# soap-disp-mega.net
KiCad netlist of a schematic drawn in EasyEDA
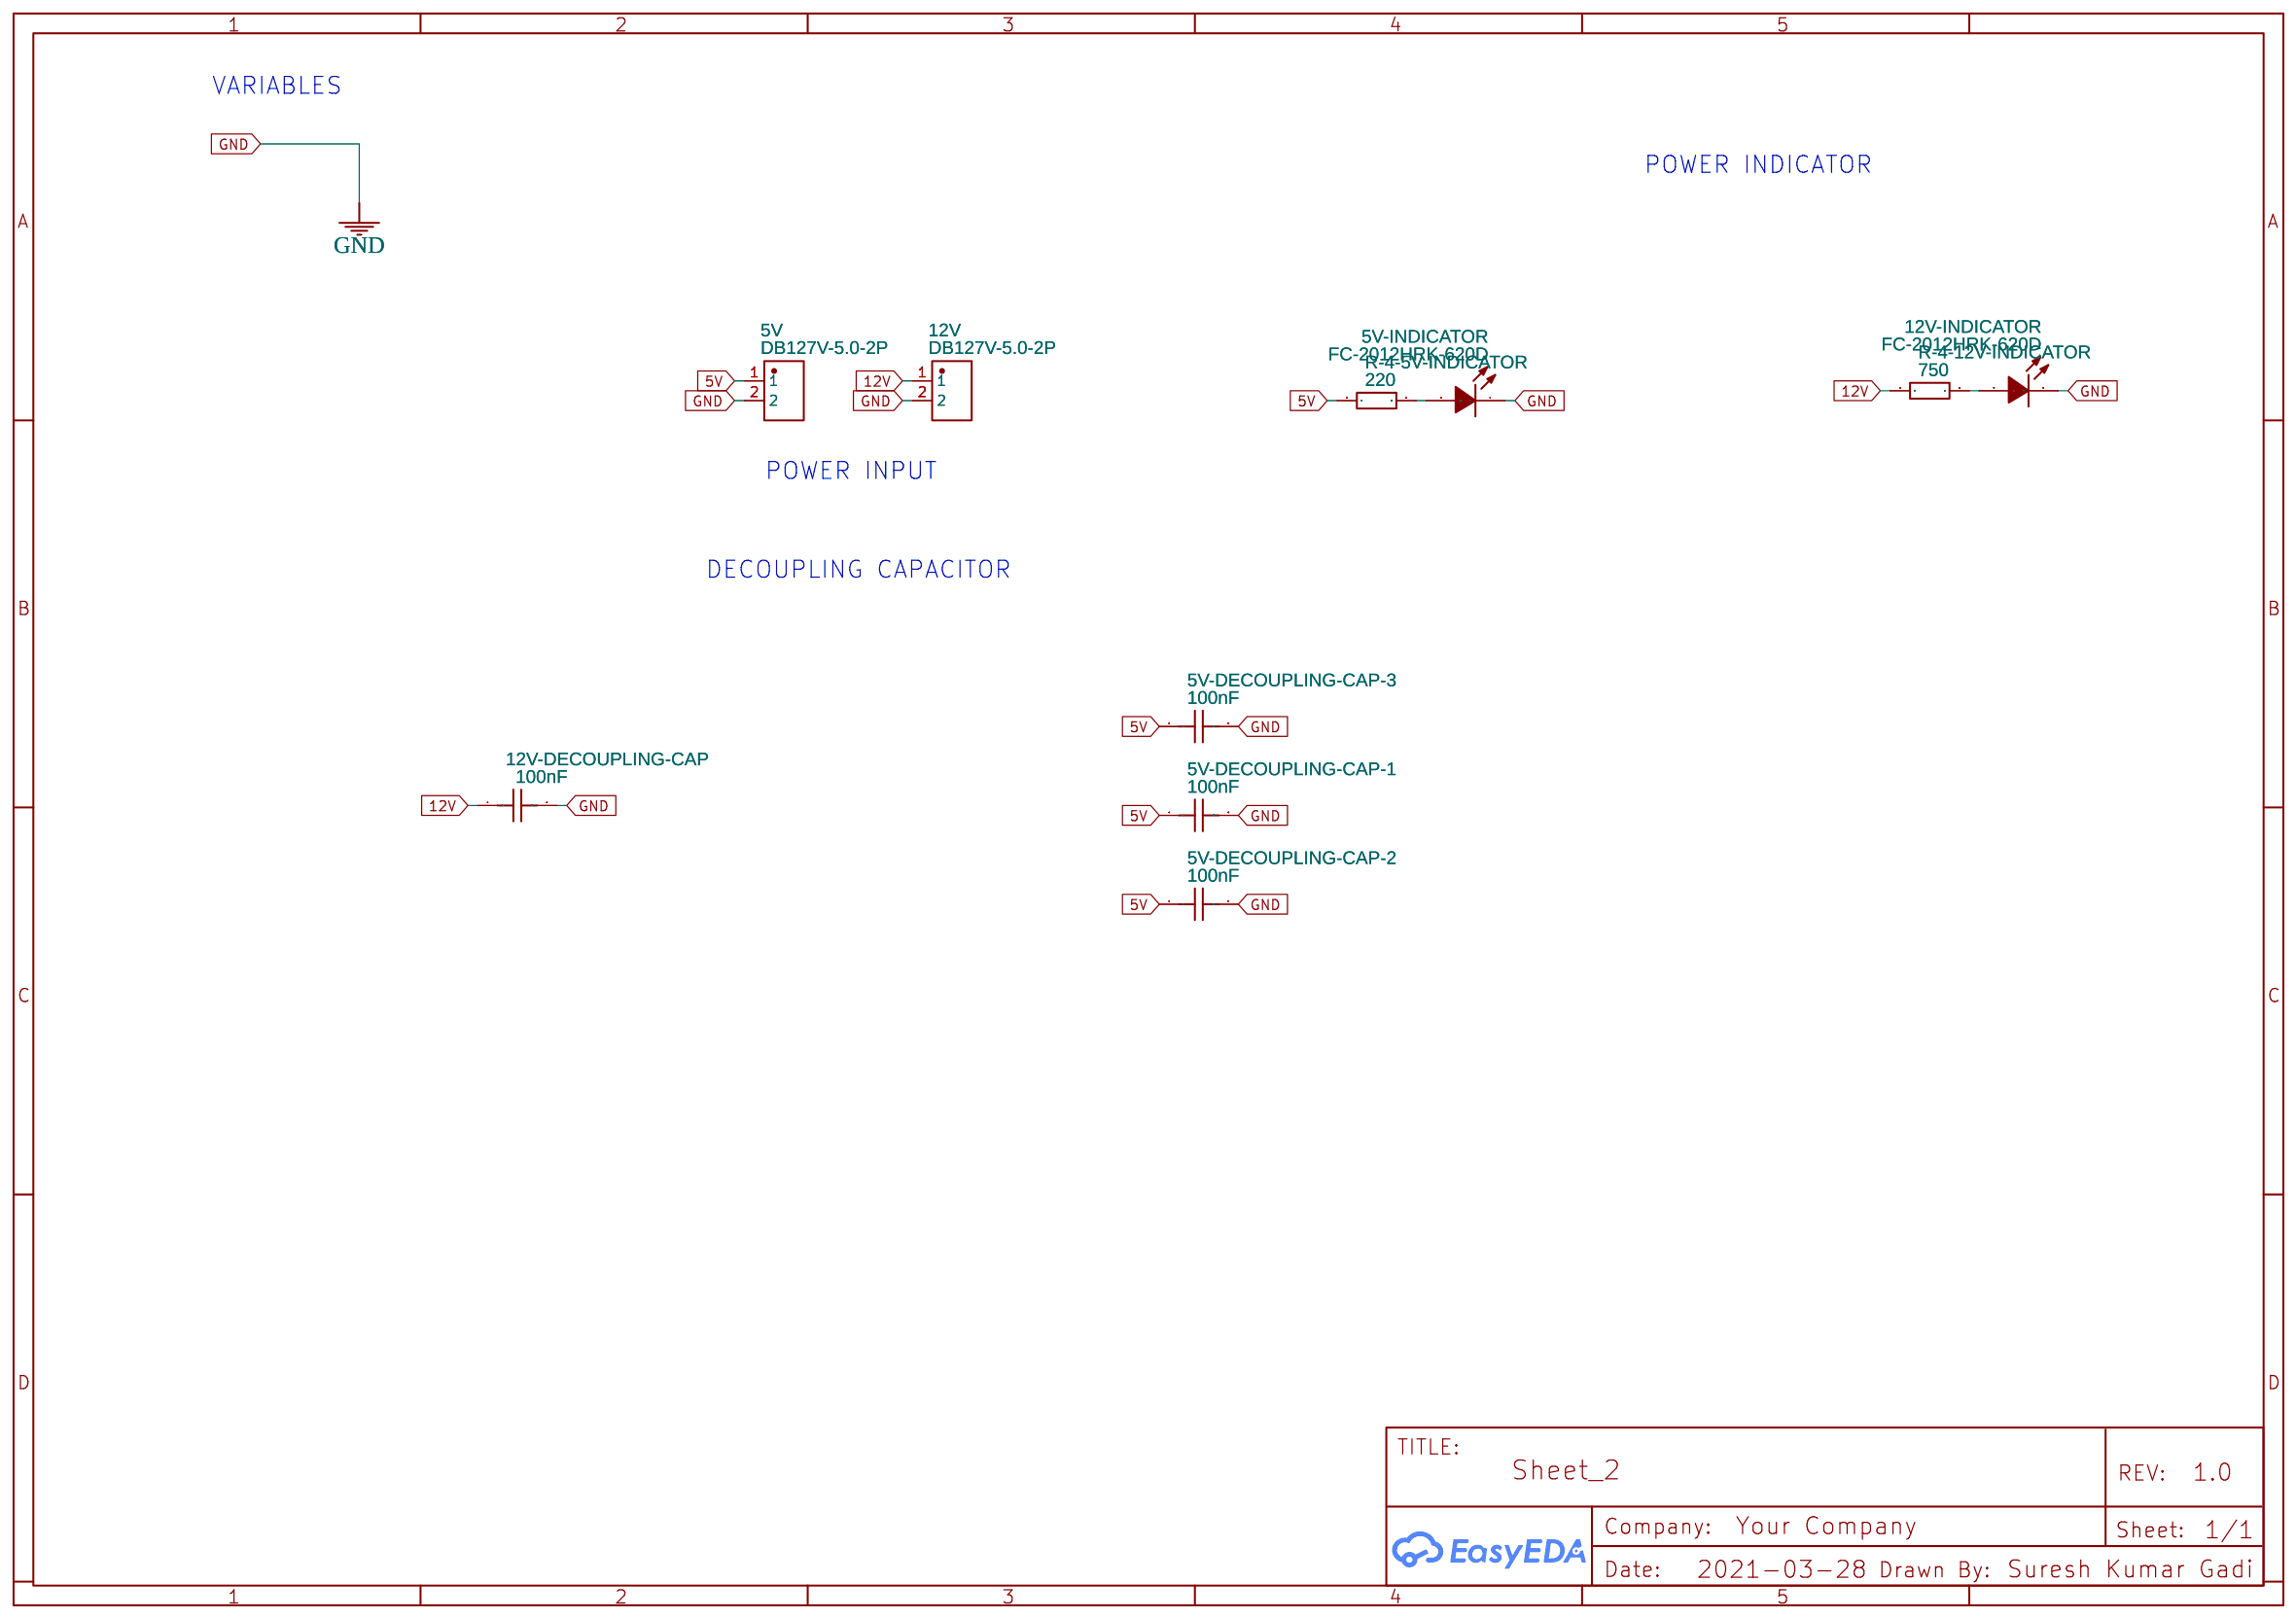
[diagram p0: Power]
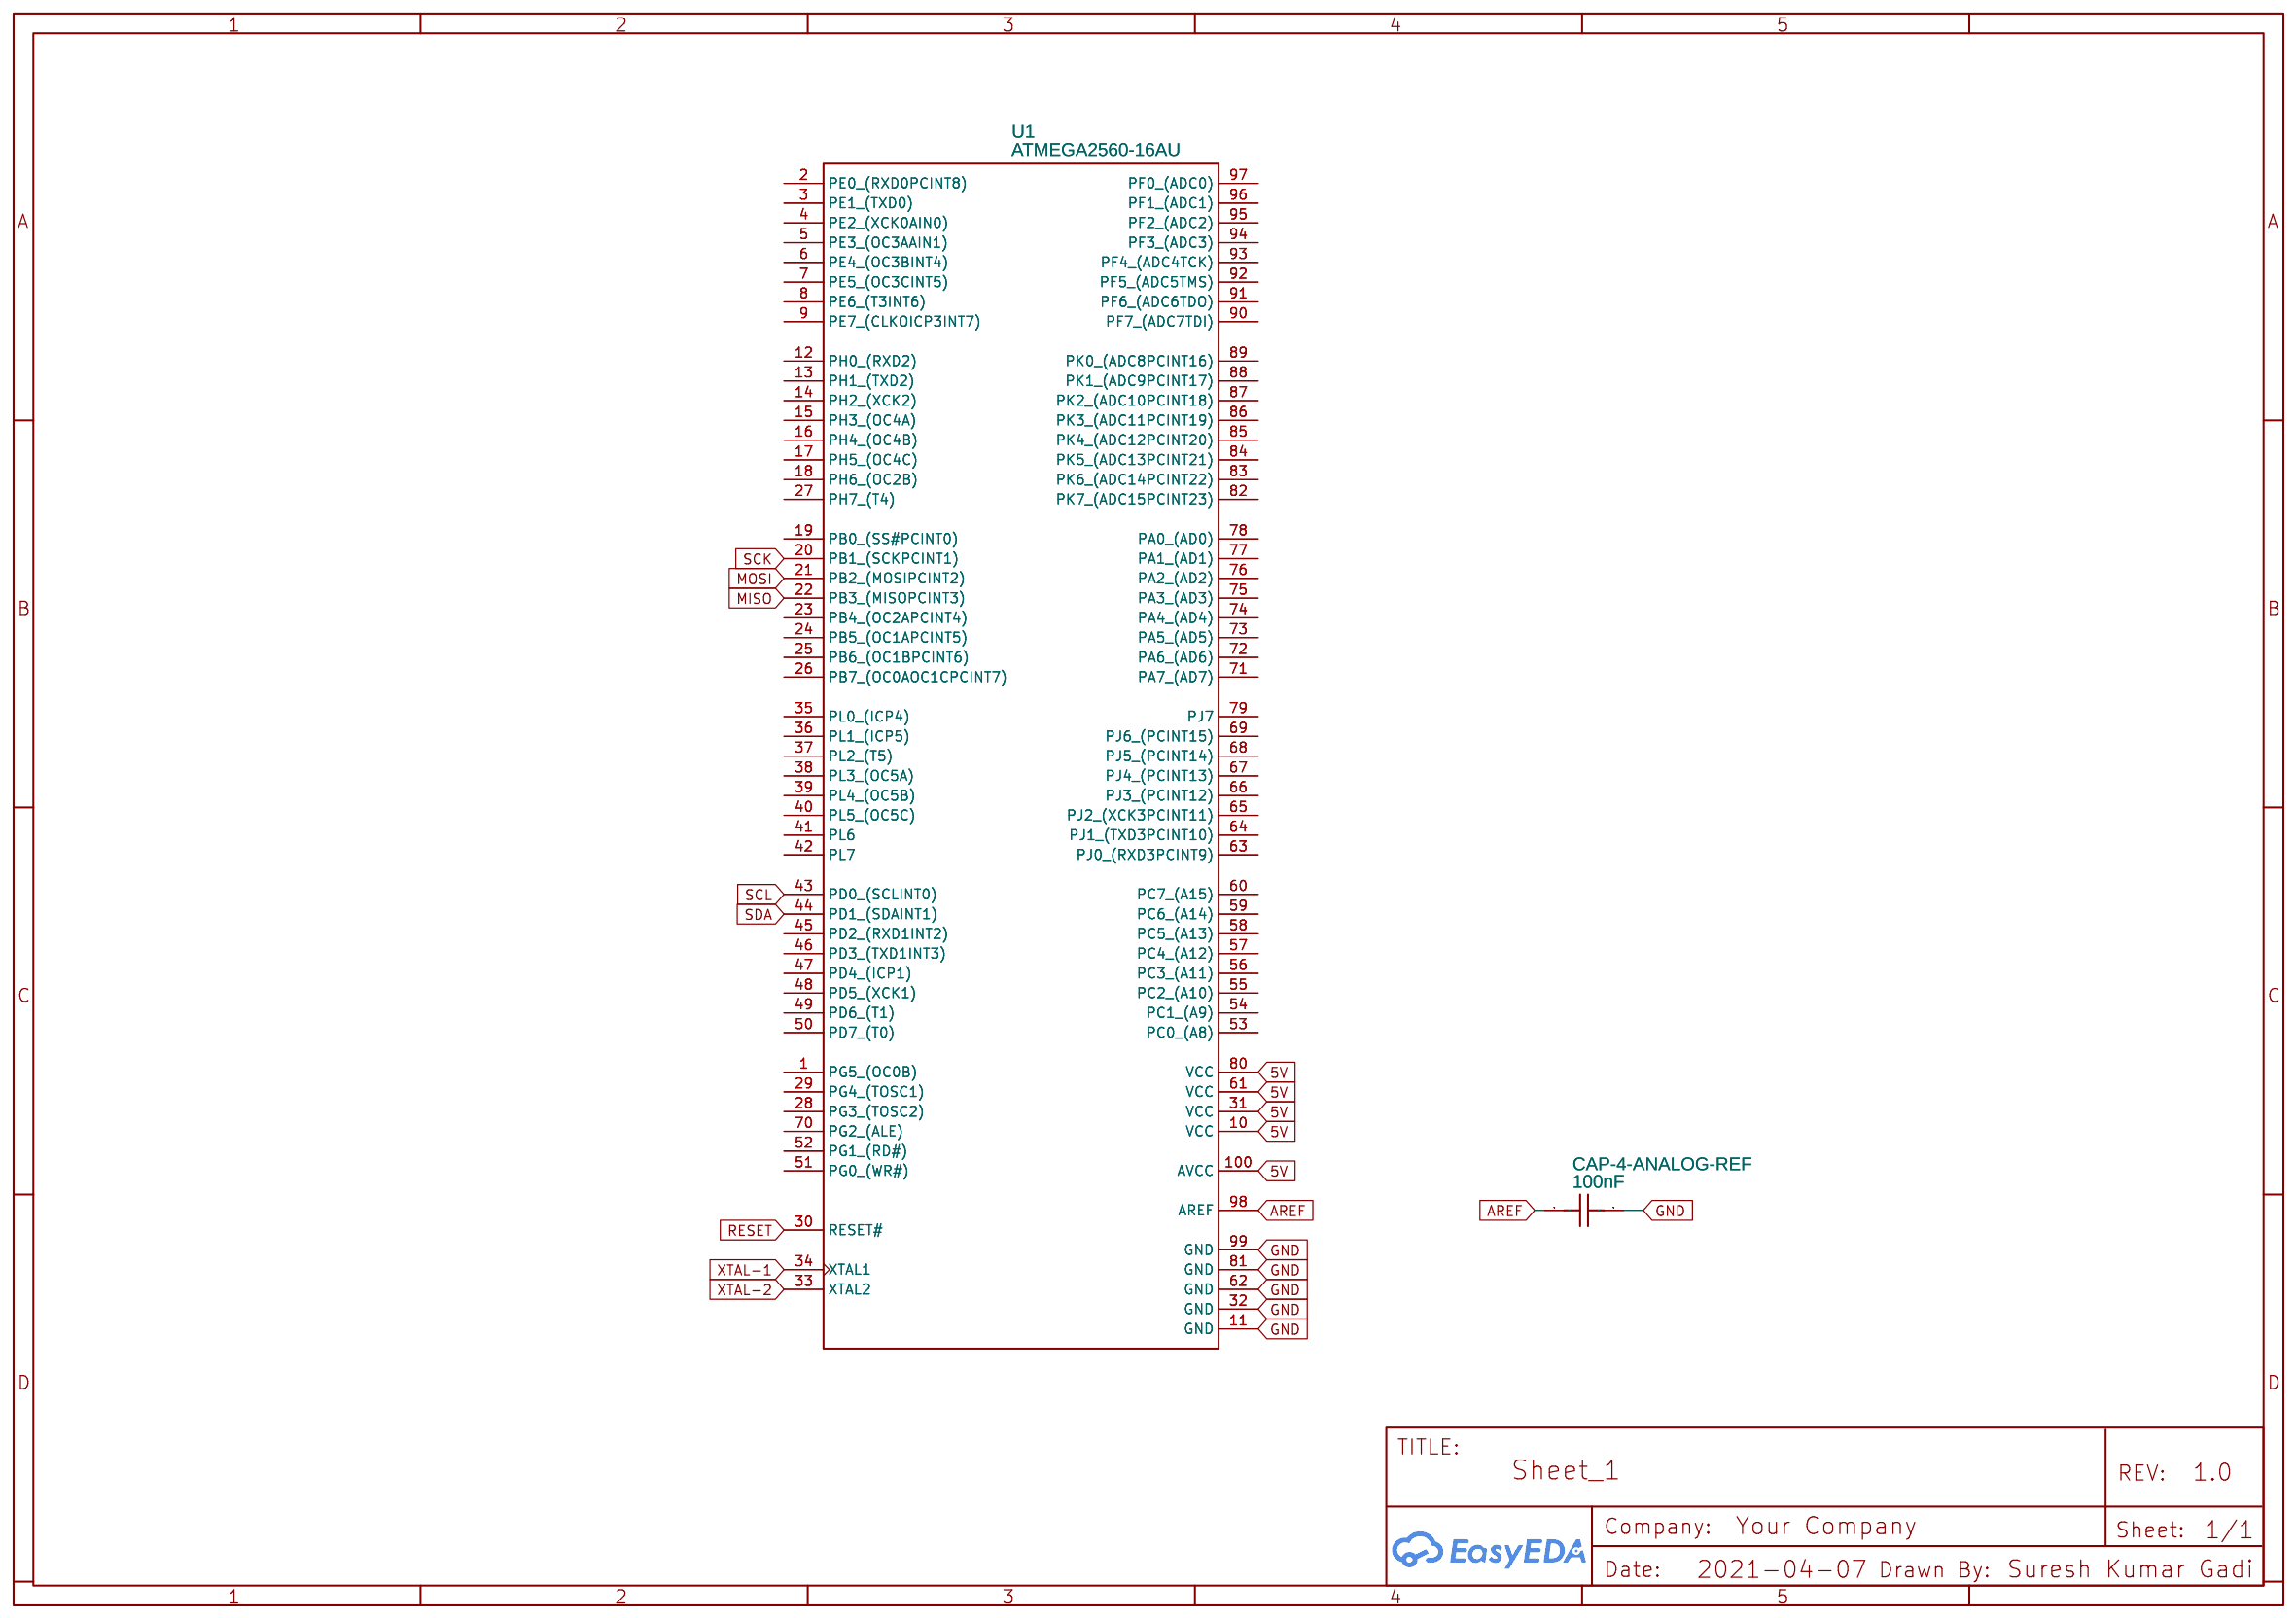
[diagram p1: Computer]
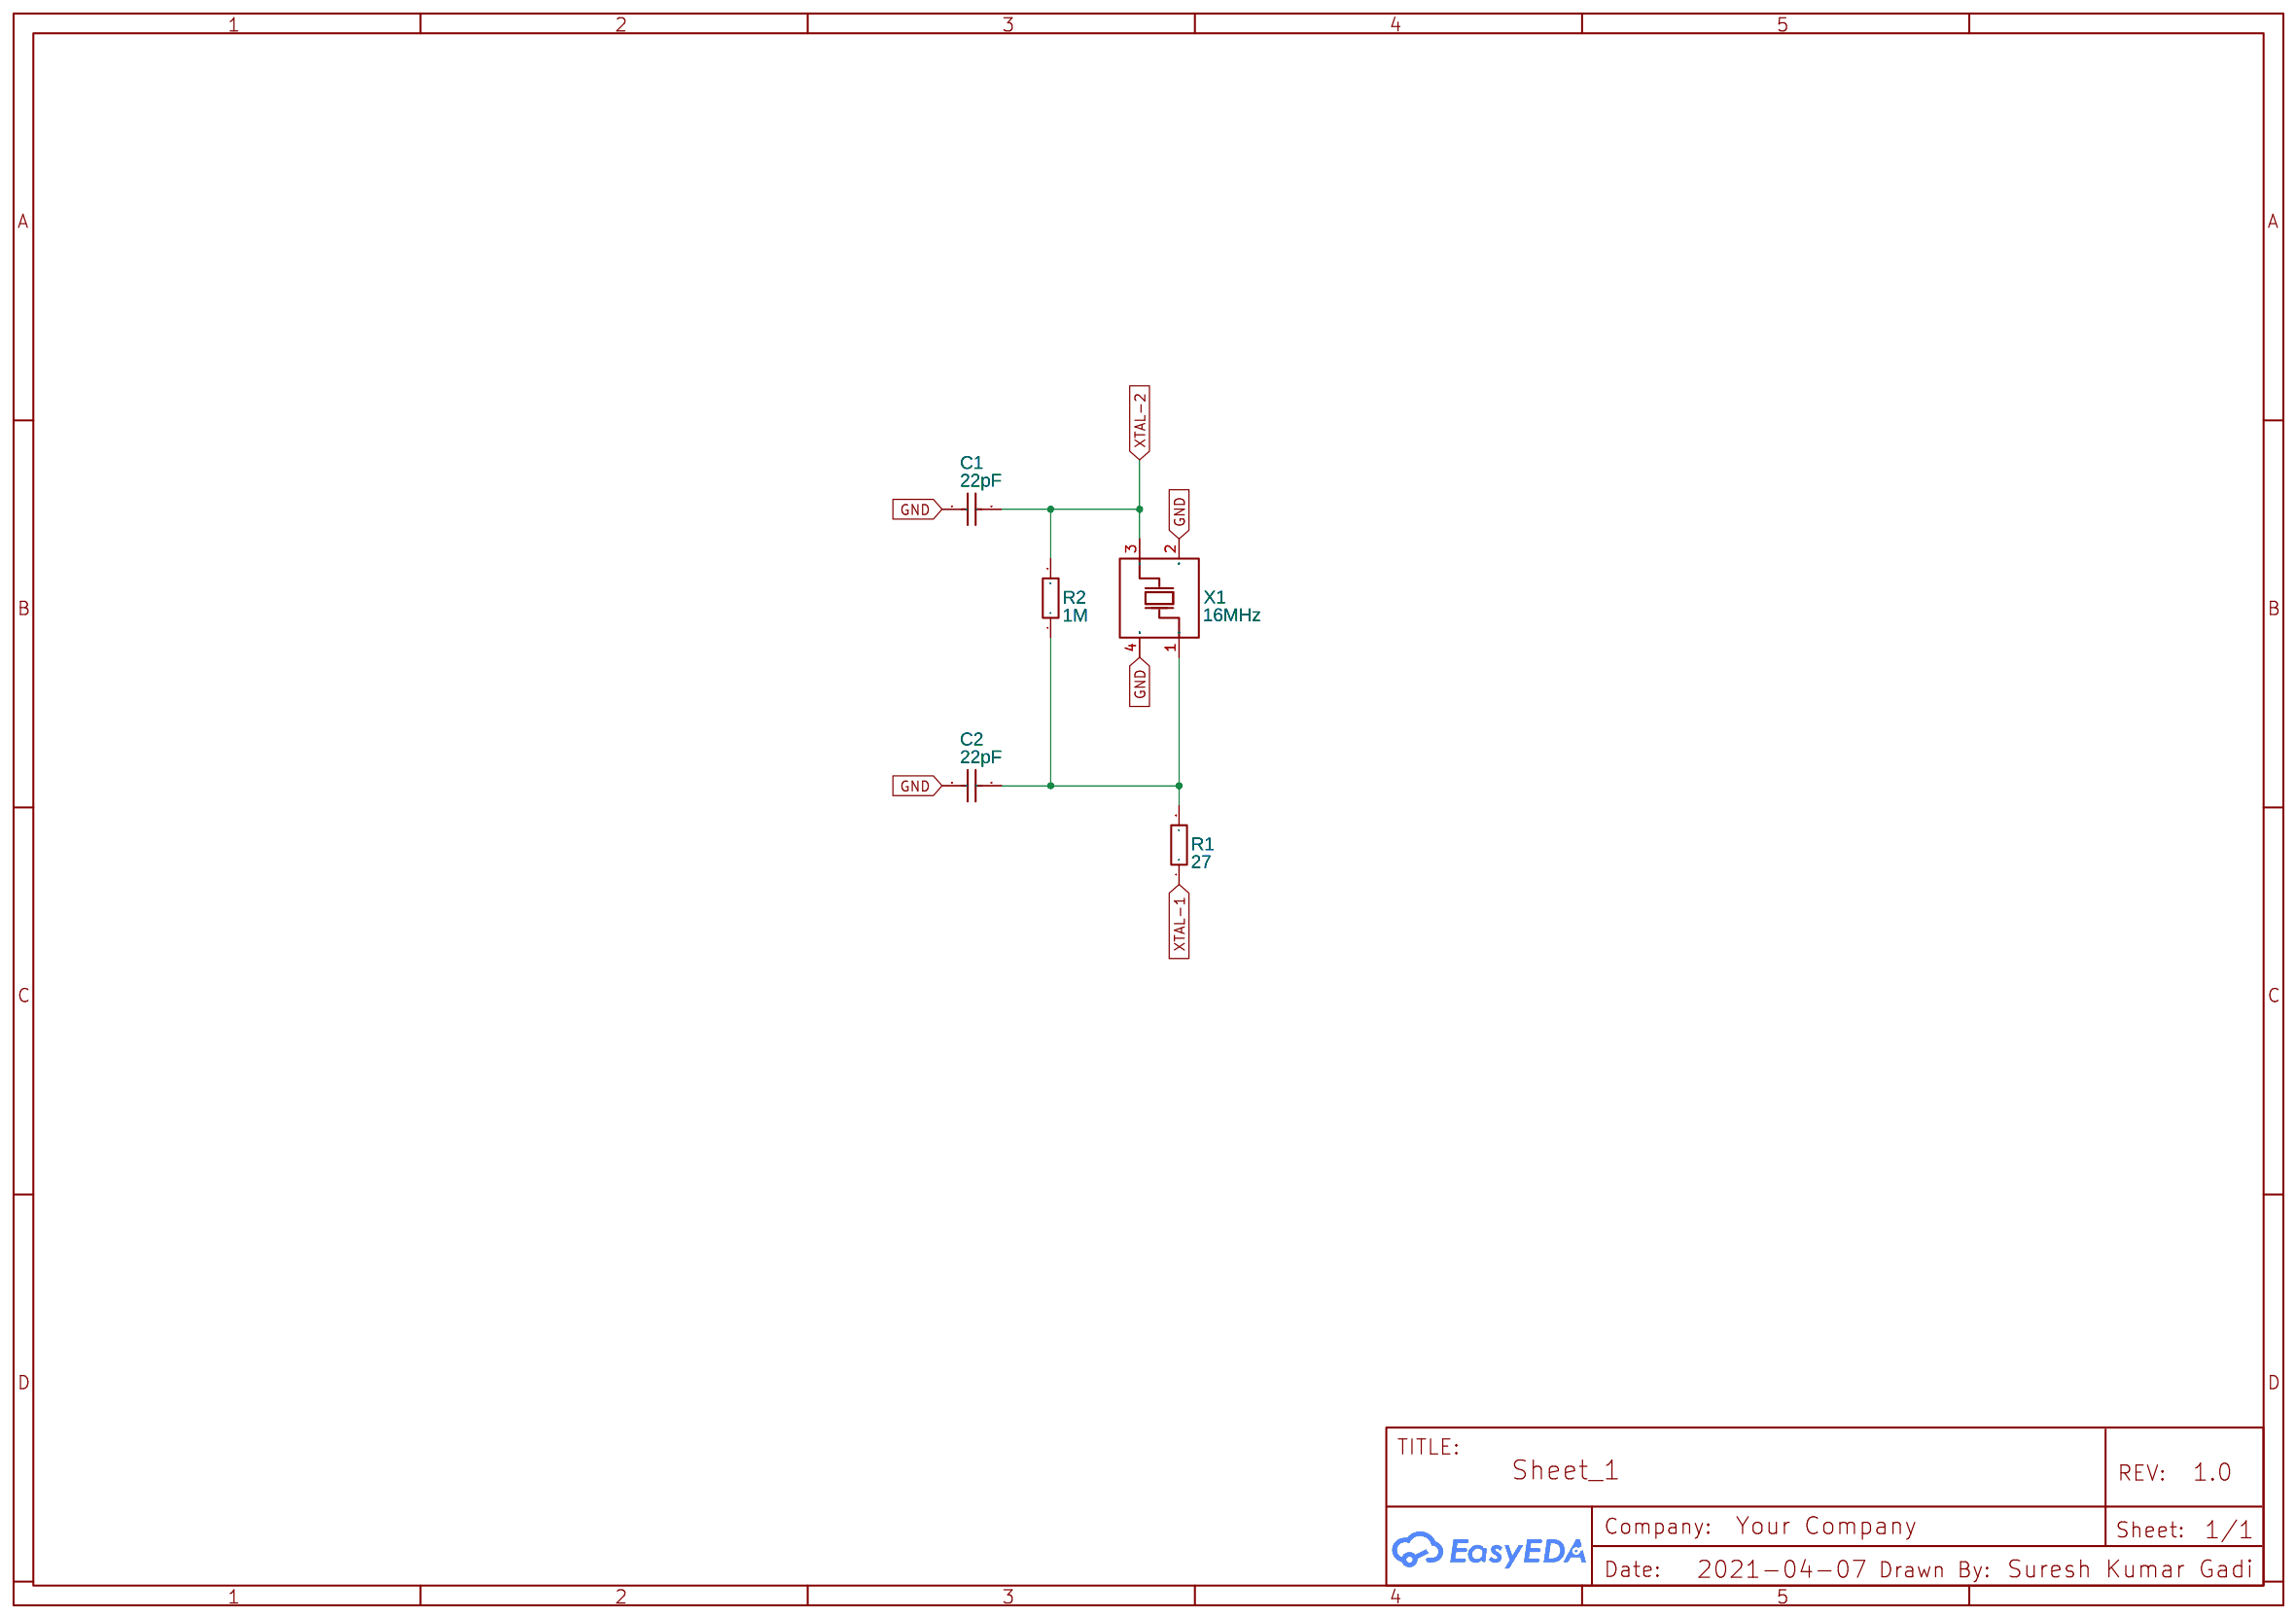
[diagram p2: Crystal]
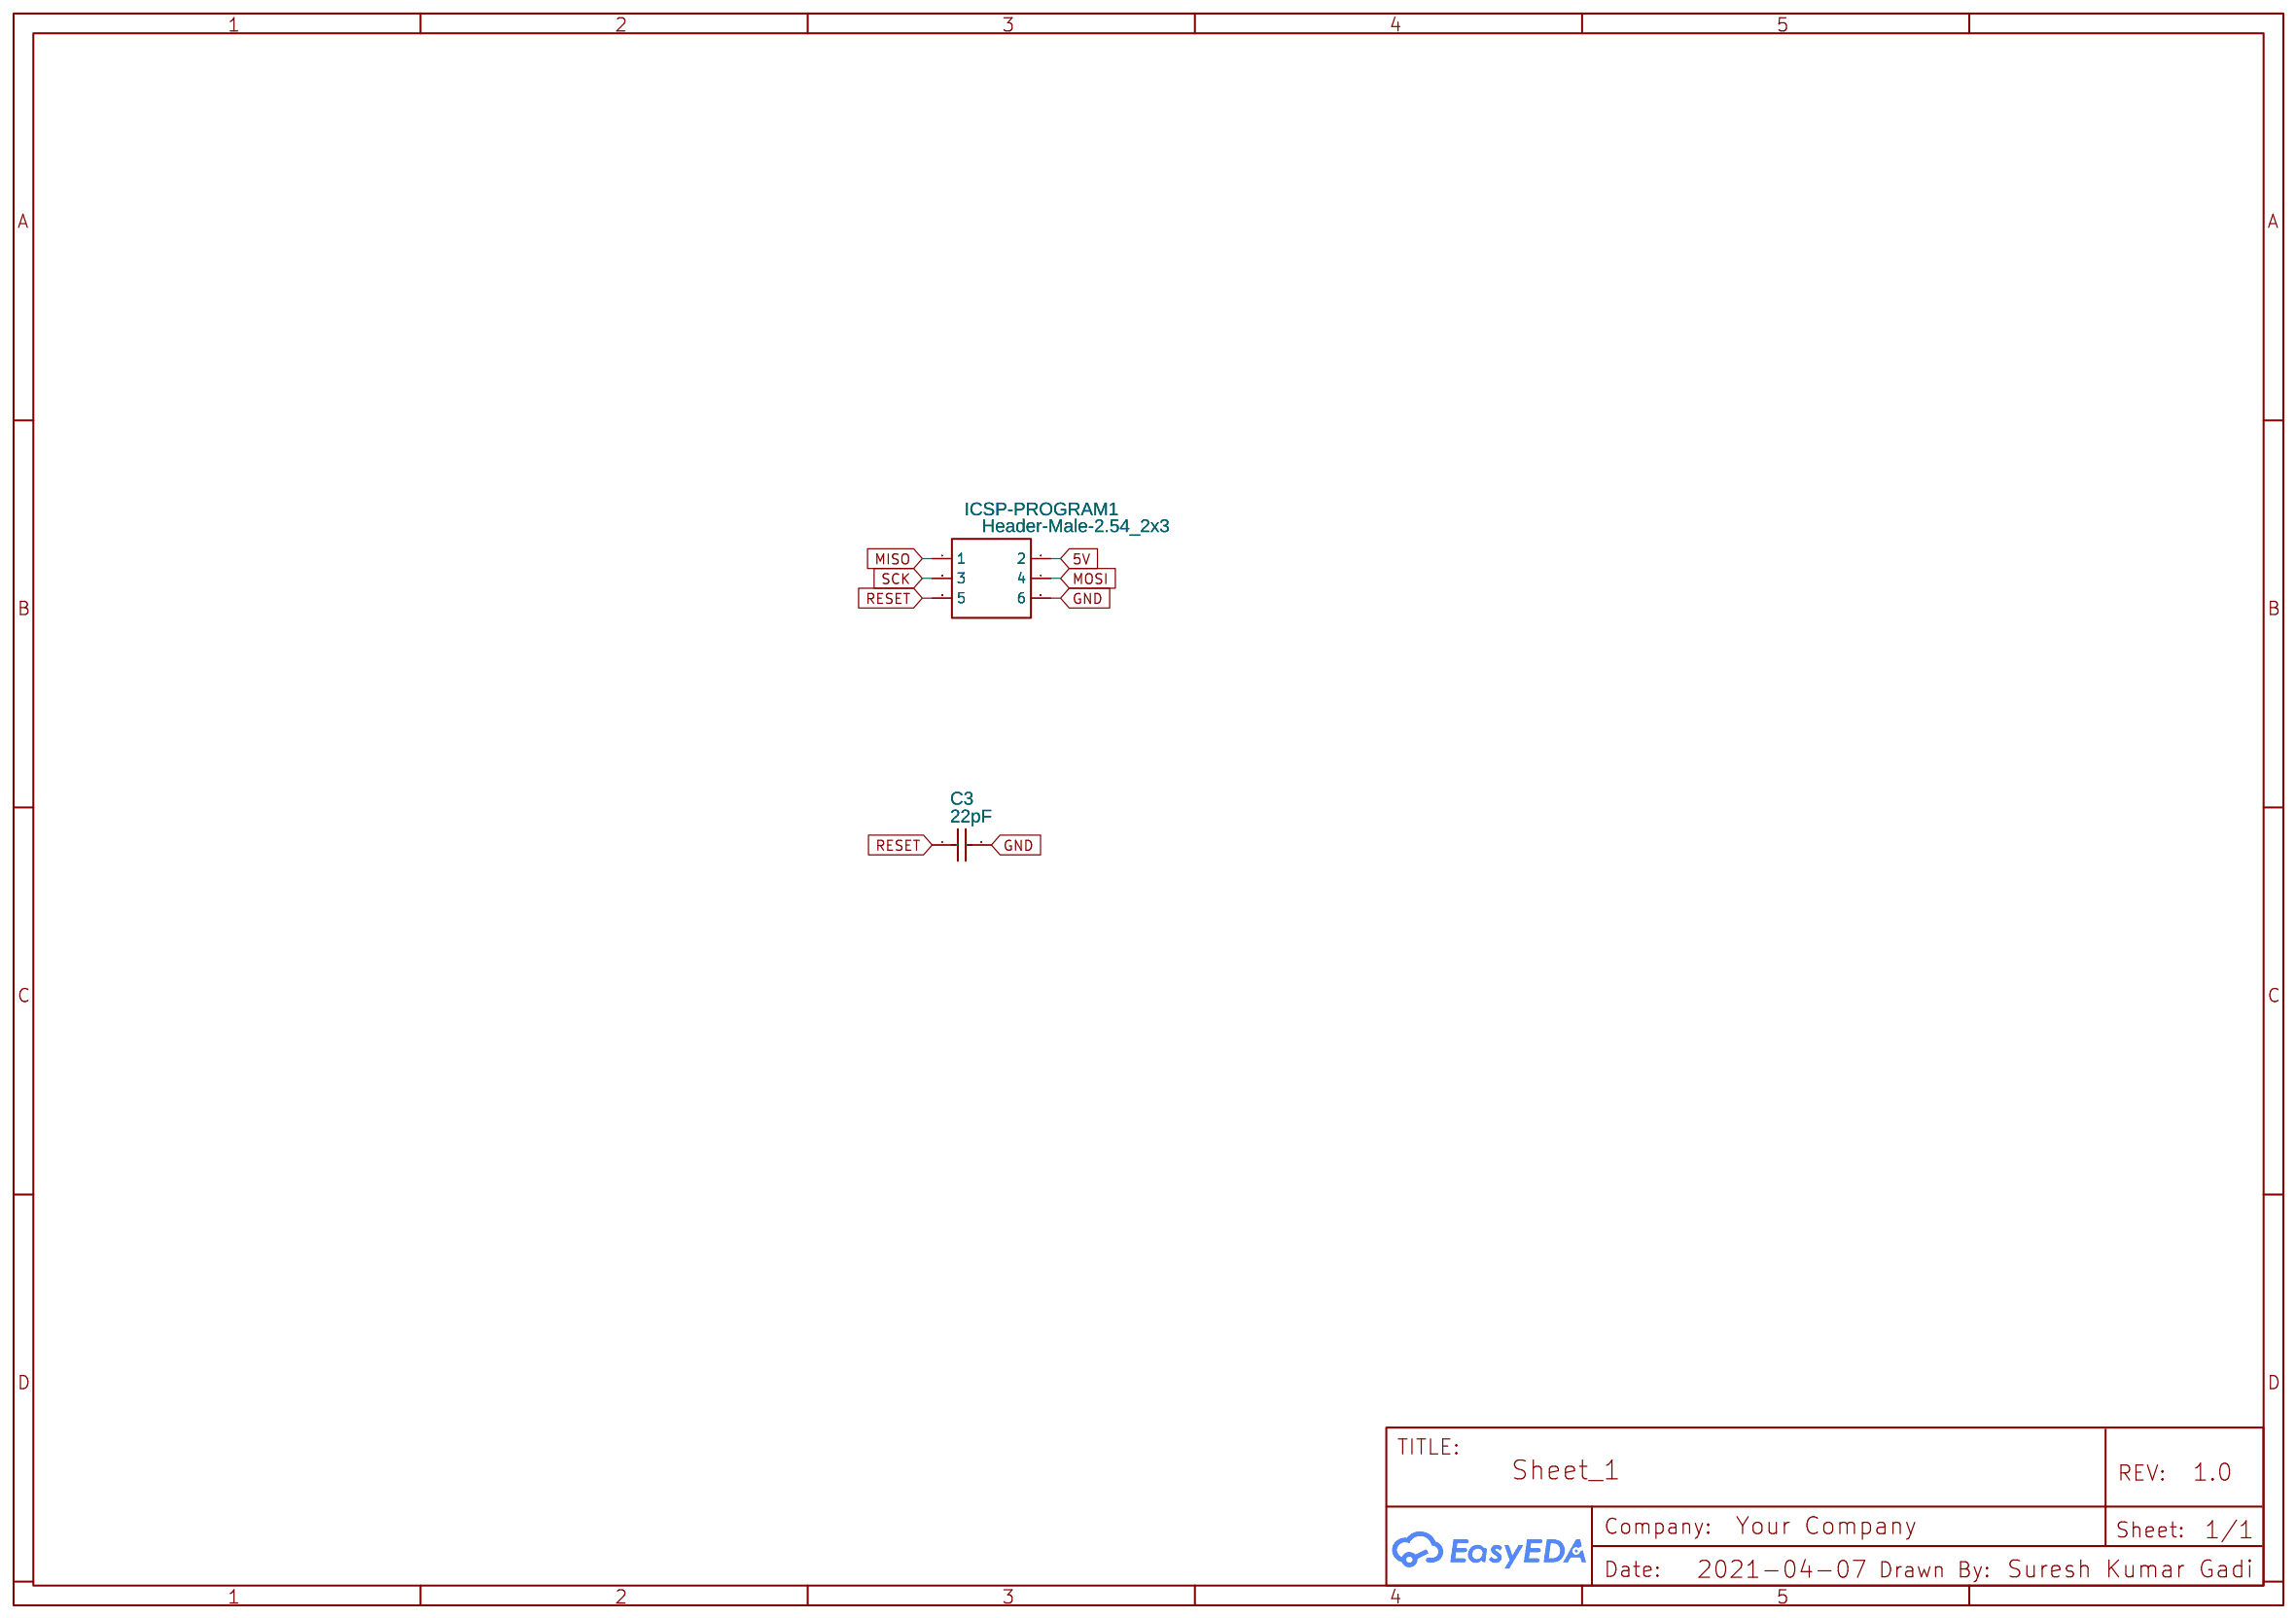
[diagram p3: ICSP]
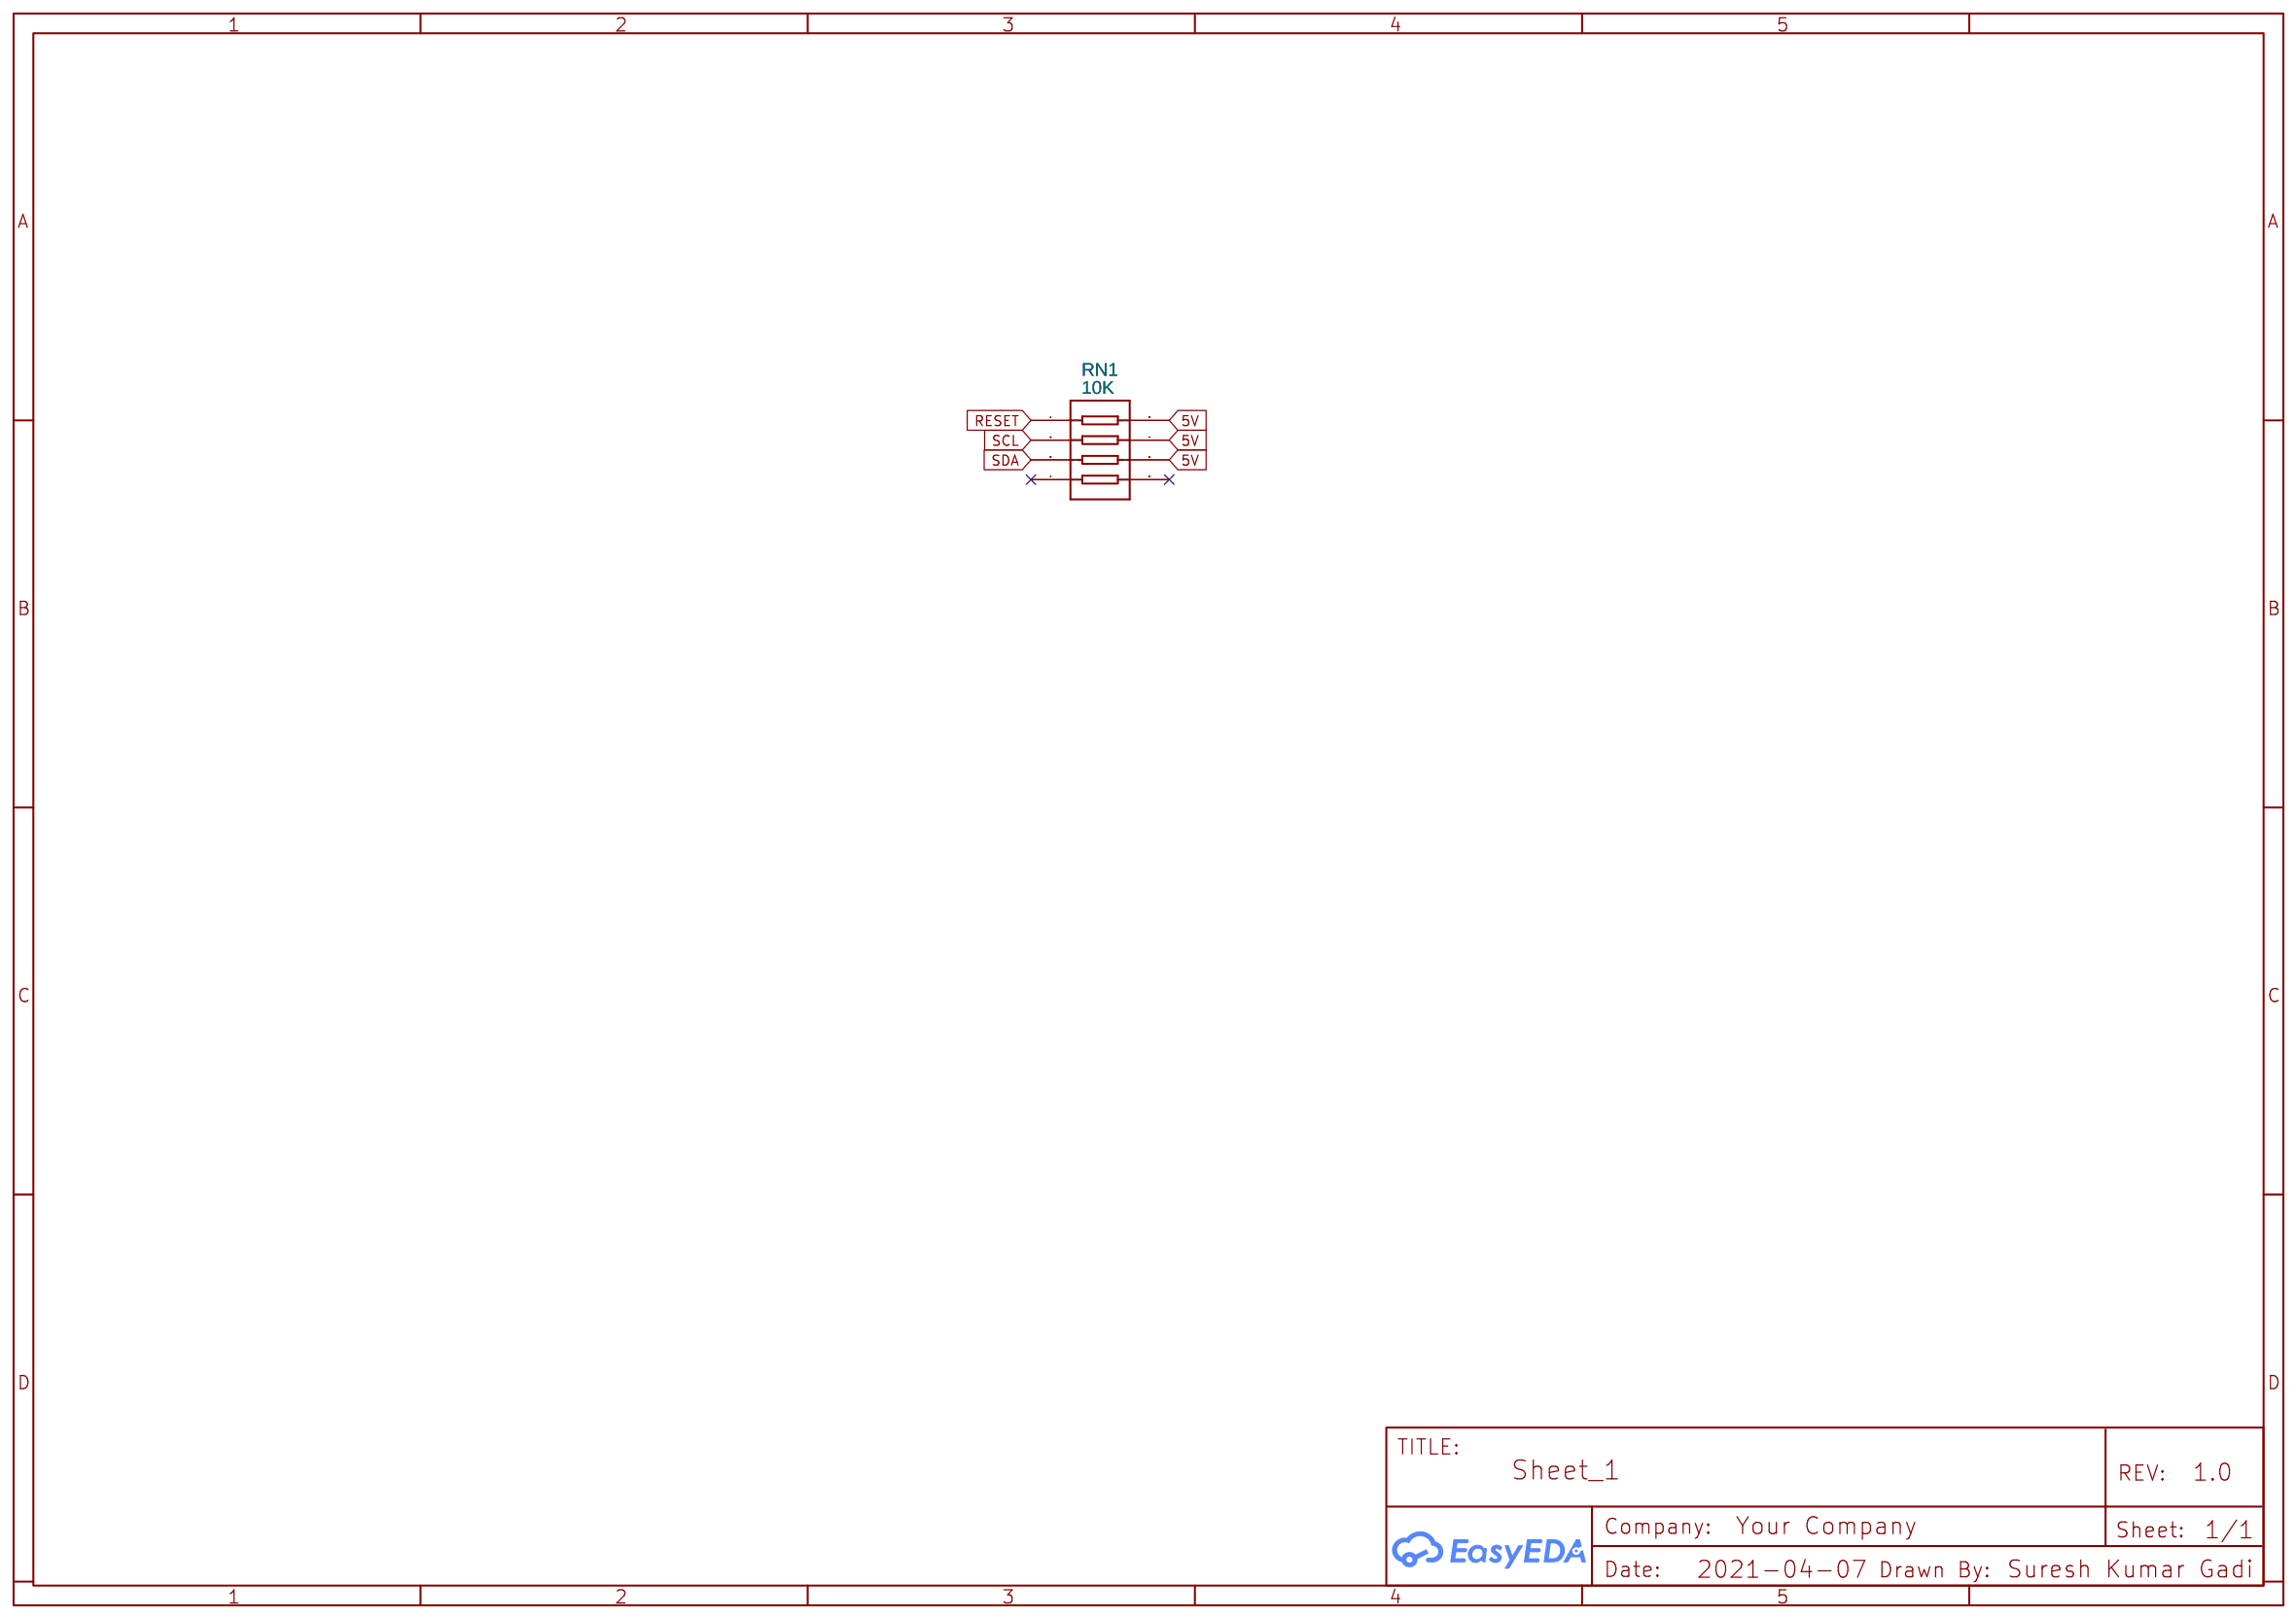
[diagram p4: Pull up/down]
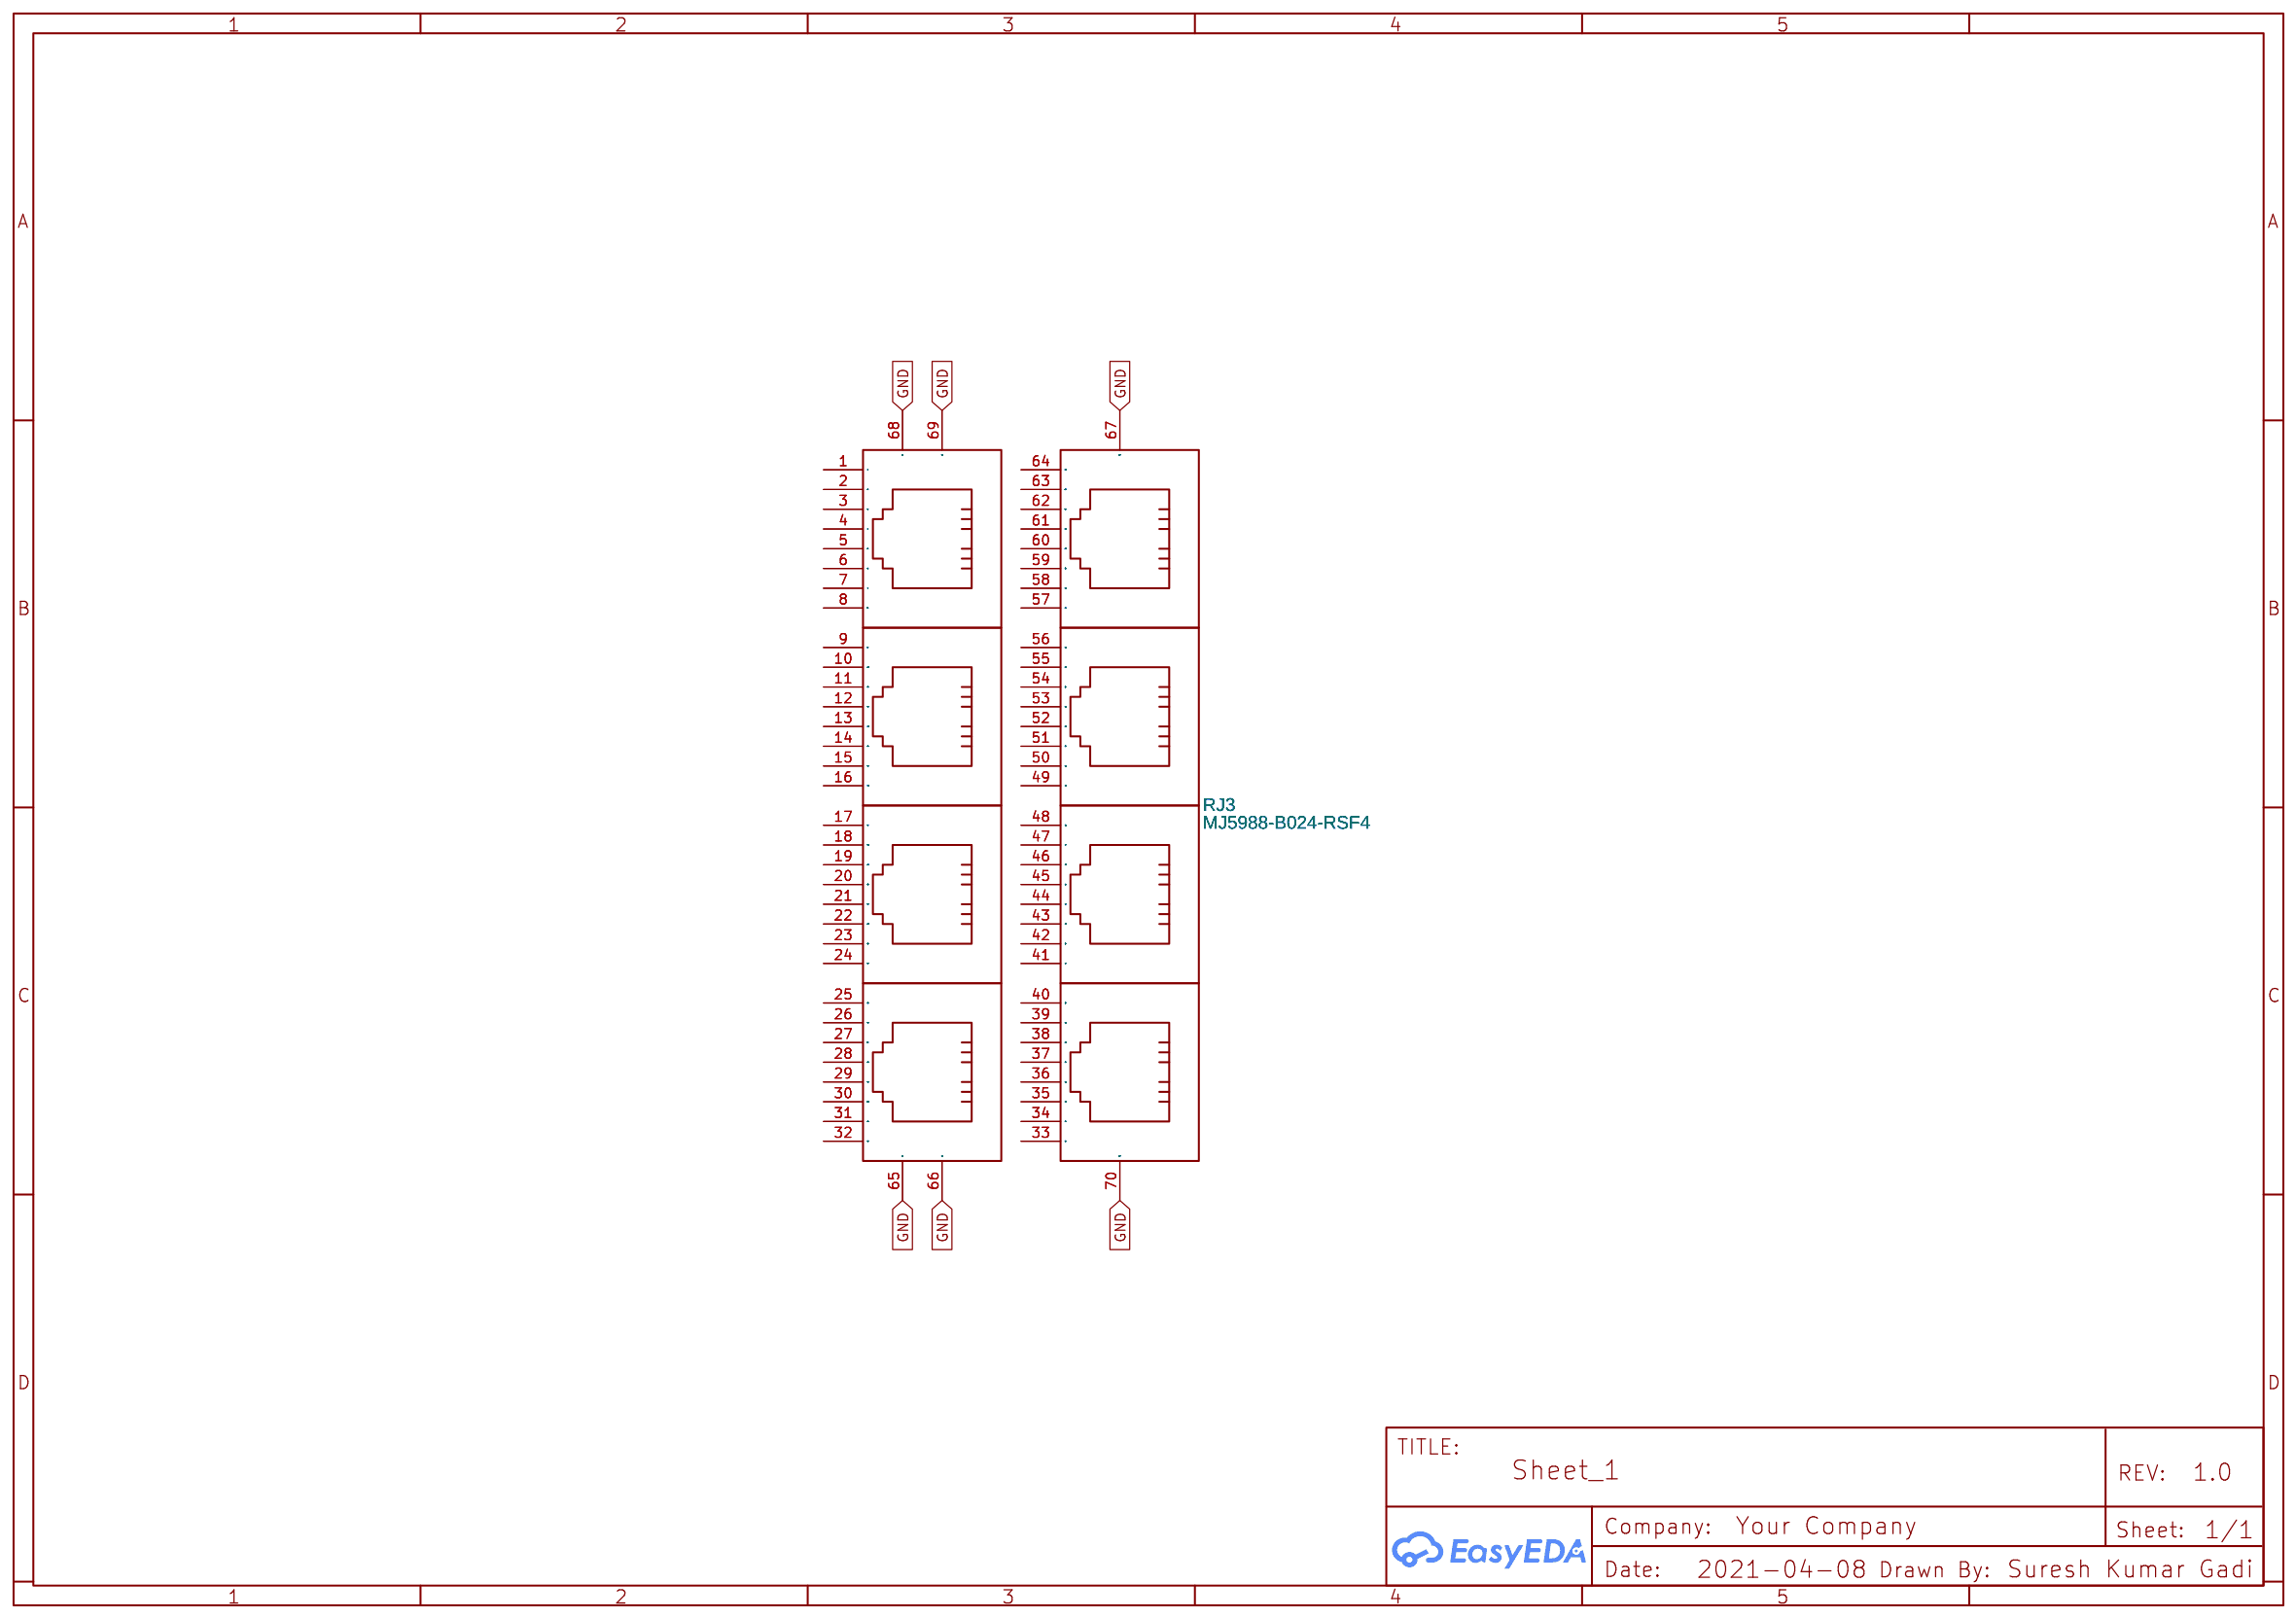
[diagram p5: Buttons]

(export (version "E")
  (design (tool "Eeschema 10.0.6"))
  (components
    (comp (ref "5V")
      (value "DB127V-5.0-2P")
      (fields (field (name "BOM_Supplier Part") "C395885"))
      (libsource (lib "") (part "DB127V-5.0-2P"))
    )
    (comp (ref "5V-DECOUPLING-CAP-1")
      (value "100nF")
      (fields
        (field (name "BOM_Manufacturer Part") "CC0603KRX7R9BB104")
        (field (name "BOM_Supplier Part") "C14663")
      )
      (libsource (lib "") (part "CC0603KRX7R9BB104"))
    )
    (comp (ref "5V-DECOUPLING-CAP-2")
      (value "100nF")
      (fields
        (field (name "BOM_Manufacturer Part") "CC0603KRX7R9BB104")
        (field (name "BOM_Supplier Part") "C14663")
      )
      (libsource (lib "") (part "CC0603KRX7R9BB104"))
    )
    (comp (ref "5V-DECOUPLING-CAP-3")
      (value "100nF")
      (fields
        (field (name "BOM_Manufacturer Part") "CC0603KRX7R9BB104")
        (field (name "BOM_Supplier Part") "C14663")
      )
      (libsource (lib "") (part "CC0603KRX7R9BB104"))
    )
    (comp (ref "5V-INDICATOR")
      (value "FC-2012HRK-620D")
      (fields (field (name "BOM_Supplier Part") "C84256"))
      (libsource (lib "") (part "FC-2012HRK-620D"))
    )
    (comp (ref "12V")
      (value "DB127V-5.0-2P")
      (fields (field (name "BOM_Supplier Part") "C395885"))
      (libsource (lib "") (part "DB127V-5.0-2P_1"))
    )
    (comp (ref "12V-DECOUPLING-CAP")
      (value "100nF")
      (fields
        (field (name "BOM_Manufacturer Part") "CC0603KRX7R9BB104")
        (field (name "BOM_Supplier Part") "C14663")
      )
      (libsource (lib "") (part "CC0603KRX7R9BB104_1"))
    )
    (comp (ref "12V-INDICATOR")
      (value "FC-2012HRK-620D")
      (fields (field (name "BOM_Supplier Part") "C84256"))
      (libsource (lib "") (part "FC-2012HRK-620D_1"))
    )
    (comp (ref "R-4-5V-INDICATOR")
      (value "220")
      (fields
        (field (name "BOM_Manufacturer Part") "0805W8F2200T5E")
        (field (name "BOM_Supplier Part") "C17557")
      )
      (libsource (lib "") (part "0805W8F2200T5E"))
    )
    (comp (ref "R-4-12V-INDICATOR")
      (value "750")
      (fields
        (field (name "BOM_Manufacturer Part") "1206W4F7500T5E")
        (field (name "BOM_Supplier Part") "C17985")
      )
      (libsource (lib "") (part "1206W4F7500T5E"))
    )
    (comp (ref "CAP-4-ANALOG-REF")
      (value "100nF")
      (fields
        (field (name "BOM_Manufacturer Part") "CC0603KRX7R9BB104")
        (field (name "BOM_Supplier Part") "C14663")
      )
      (libsource (lib "") (part "CC0603KRX7R9BB104"))
    )
    (comp (ref "U1")
      (value "ATMEGA2560-16AU")
      (fields (field (name "BOM_Supplier Part") "C22460"))
      (libsource (lib "") (part "ATMEGA2560-16AU"))
    )
    (comp (ref "C1")
      (value "22pF")
      (fields
        (field (name "BOM_Manufacturer Part") "CL21C220JBANNNC")
        (field (name "BOM_Supplier Part") "C1804")
      )
      (libsource (lib "") (part "CL21C220JBANNNC"))
    )
    (comp (ref "C2")
      (value "22pF")
      (fields
        (field (name "BOM_Manufacturer Part") "CL21C220JBANNNC")
        (field (name "BOM_Supplier Part") "C1804")
      )
      (libsource (lib "") (part "CL21C220JBANNNC"))
    )
    (comp (ref "R1")
      (value "27")
      (fields
        (field (name "BOM_Manufacturer Part") "0603WAF270JT5E")
        (field (name "BOM_Supplier Part") "C25190")
      )
      (libsource (lib "") (part "0603WAF270JT5E"))
    )
    (comp (ref "R2")
      (value "1M")
      (fields
        (field (name "BOM_Manufacturer Part") "0805W8F1004T5E")
        (field (name "BOM_Supplier Part") "C17514")
      )
      (libsource (lib "") (part "0805W8F1004T5E"))
    )
    (comp (ref "X1")
      (value "16MHz")
      (fields
        (field (name "BOM_Manufacturer Part") "X322516MLB4SI")
        (field (name "BOM_Supplier Part") "C13738")
      )
      (libsource (lib "") (part "X322516MLB4SI"))
    )
    (comp (ref "C3")
      (value "22pF")
      (fields
        (field (name "BOM_Manufacturer Part") "CL21C220JBANNNC")
        (field (name "BOM_Supplier Part") "C1804")
      )
      (libsource (lib "") (part "CL21C220JBANNNC"))
    )
    (comp (ref "ICSP-PROGRAM1")
      (value "Header-Male-2.54_2x3")
      (fields (field (name "BOM_Supplier Part") "C65114"))
      (libsource (lib "") (part "Header-Male-2.54_2x3"))
    )
    (comp (ref "RN1")
      (value "10K")
      (fields
        (field (name "BOM_Manufacturer Part") "4D03WGJ0103T5E")
        (field (name "BOM_Supplier Part") "C29718")
      )
      (libsource (lib "") (part "4D03WGJ0103T5E"))
    )
    (comp (ref "RJ3")
      (value "MJ5988-B024-RSF4")
      (fields (field (name "BOM_Supplier Part") "C528693"))
      (libsource (lib "") (part "MJ5988-B024-RSF4"))
    )
  )
  (nets
    (net (code "1") (name "5V") (class "Default")
      (node (ref "5V") (pin "1") (pinfunction "1_1") (pintype "unspecified"))
      (node (ref "5V-DECOUPLING-CAP-1") (pin "1") (pinfunction "1_1") (pintype "unspecified"))
      (node (ref "5V-DECOUPLING-CAP-2") (pin "1") (pinfunction "1_1") (pintype "unspecified"))
      (node (ref "5V-DECOUPLING-CAP-3") (pin "1") (pinfunction "1_1") (pintype "unspecified"))
      (node (ref "ICSP-PROGRAM1") (pin "2") (pinfunction "2_2") (pintype "input"))
      (node (ref "R-4-5V-INDICATOR") (pin "1") (pinfunction "1_1") (pintype "input"))
      (node (ref "RN1") (pin "6") (pinfunction "6_6") (pintype "input"))
      (node (ref "RN1") (pin "7") (pinfunction "7_7") (pintype "input"))
      (node (ref "RN1") (pin "8") (pinfunction "8_8") (pintype "input"))
      (node (ref "U1") (pin "10") (pinfunction "VCC_10") (pintype "passive"))
      (node (ref "U1") (pin "100") (pinfunction "AVCC_100") (pintype "passive"))
      (node (ref "U1") (pin "31") (pinfunction "VCC_31") (pintype "passive"))
      (node (ref "U1") (pin "61") (pinfunction "VCC_61") (pintype "passive"))
      (node (ref "U1") (pin "80") (pinfunction "VCC_80") (pintype "passive"))
    )
    (net (code "2") (name "12V") (class "Default")
      (node (ref "12V") (pin "1") (pinfunction "1_1") (pintype "unspecified"))
      (node (ref "12V-DECOUPLING-CAP") (pin "1") (pinfunction "1_1") (pintype "unspecified"))
      (node (ref "R-4-12V-INDICATOR") (pin "1") (pinfunction "1_1") (pintype "input"))
    )
    (net (code "3") (name "AREF") (class "Default")
      (node (ref "CAP-4-ANALOG-REF") (pin "1") (pinfunction "1_1") (pintype "unspecified"))
      (node (ref "U1") (pin "98") (pinfunction "AREF_98") (pintype "passive"))
    )
    (net (code "4") (name "GND") (class "Default")
      (node (ref "12V") (pin "2") (pinfunction "2_2") (pintype "unspecified"))
      (node (ref "12V-DECOUPLING-CAP") (pin "2") (pinfunction "2_2") (pintype "unspecified"))
      (node (ref "12V-INDICATOR") (pin "1") (pinfunction "-_1") (pintype "unspecified"))
      (node (ref "5V") (pin "2") (pinfunction "2_2") (pintype "unspecified"))
      (node (ref "5V-DECOUPLING-CAP-1") (pin "2") (pinfunction "2_2") (pintype "unspecified"))
      (node (ref "5V-DECOUPLING-CAP-2") (pin "2") (pinfunction "2_2") (pintype "unspecified"))
      (node (ref "5V-DECOUPLING-CAP-3") (pin "2") (pinfunction "2_2") (pintype "unspecified"))
      (node (ref "5V-INDICATOR") (pin "1") (pinfunction "-_1") (pintype "unspecified"))
      (node (ref "C1") (pin "1") (pinfunction "1_1") (pintype "input"))
      (node (ref "C2") (pin "1") (pinfunction "1_1") (pintype "input"))
      (node (ref "C3") (pin "2") (pinfunction "2_2") (pintype "input"))
      (node (ref "CAP-4-ANALOG-REF") (pin "2") (pinfunction "2_2") (pintype "unspecified"))
      (node (ref "ICSP-PROGRAM1") (pin "6") (pinfunction "6_6") (pintype "input"))
      (node (ref "RJ3") (pin "65") (pinfunction "65_65") (pintype "unspecified"))
      (node (ref "RJ3") (pin "66") (pinfunction "66_66") (pintype "unspecified"))
      (node (ref "RJ3") (pin "67") (pinfunction "67_67") (pintype "unspecified"))
      (node (ref "RJ3") (pin "68") (pinfunction "68_68") (pintype "unspecified"))
      (node (ref "RJ3") (pin "69") (pinfunction "69_69") (pintype "unspecified"))
      (node (ref "RJ3") (pin "70") (pinfunction "70_70") (pintype "unspecified"))
      (node (ref "U1") (pin "11") (pinfunction "GND_11") (pintype "passive"))
      (node (ref "U1") (pin "32") (pinfunction "GND_32") (pintype "passive"))
      (node (ref "U1") (pin "62") (pinfunction "GND_62") (pintype "passive"))
      (node (ref "U1") (pin "81") (pinfunction "GND_81") (pintype "passive"))
      (node (ref "U1") (pin "99") (pinfunction "GND_99") (pintype "passive"))
      (node (ref "X1") (pin "2") (pinfunction "GND_2") (pintype "unspecified"))
      (node (ref "X1") (pin "4") (pinfunction "GND_4") (pintype "unspecified"))
    )
    (net (code "5") (name "MISO") (class "Default")
      (node (ref "ICSP-PROGRAM1") (pin "1") (pinfunction "1_1") (pintype "input"))
      (node (ref "U1") (pin "22") (pinfunction "PB3_(MISOPCINT3)_22") (pintype "bidirectional"))
    )
    (net (code "6") (name "MOSI") (class "Default")
      (node (ref "ICSP-PROGRAM1") (pin "4") (pinfunction "4_4") (pintype "input"))
      (node (ref "U1") (pin "21") (pinfunction "PB2_(MOSIPCINT2)_21") (pintype "bidirectional"))
    )
    (net (code "7") (name "Net-(5V-INDICATOR-+)") (class "Default")
      (node (ref "5V-INDICATOR") (pin "2") (pinfunction "+_2") (pintype "unspecified"))
      (node (ref "R-4-5V-INDICATOR") (pin "2") (pinfunction "2_2") (pintype "input"))
    )
    (net (code "8") (name "Net-(12V-INDICATOR-+)") (class "Default")
      (node (ref "12V-INDICATOR") (pin "2") (pinfunction "+_2") (pintype "unspecified"))
      (node (ref "R-4-12V-INDICATOR") (pin "2") (pinfunction "2_2") (pintype "input"))
    )
    (net (code "9") (name "Net-(X1-OSC1)") (class "Default")
      (node (ref "C2") (pin "2") (pinfunction "2_2") (pintype "input"))
      (node (ref "R1") (pin "2") (pinfunction "2_2") (pintype "input"))
      (node (ref "R2") (pin "1") (pinfunction "1_1") (pintype "input"))
      (node (ref "X1") (pin "1") (pinfunction "OSC1_1") (pintype "unspecified"))
    )
    (net (code "10") (name "RESET") (class "Default")
      (node (ref "C3") (pin "1") (pinfunction "1_1") (pintype "input"))
      (node (ref "ICSP-PROGRAM1") (pin "5") (pinfunction "5_5") (pintype "input"))
      (node (ref "RN1") (pin "1") (pinfunction "1_1") (pintype "input"))
      (node (ref "U1") (pin "30") (pinfunction "RESET#_30") (pintype "unspecified"))
    )
    (net (code "11") (name "SCK") (class "Default")
      (node (ref "ICSP-PROGRAM1") (pin "3") (pinfunction "3_3") (pintype "input"))
      (node (ref "U1") (pin "20") (pinfunction "PB1_(SCKPCINT1)_20") (pintype "bidirectional"))
    )
    (net (code "12") (name "SCL") (class "Default")
      (node (ref "RN1") (pin "2") (pinfunction "2_2") (pintype "input"))
      (node (ref "U1") (pin "43") (pinfunction "PD0_(SCLINT0)_43") (pintype "bidirectional"))
    )
    (net (code "13") (name "SDA") (class "Default")
      (node (ref "RN1") (pin "3") (pinfunction "3_3") (pintype "input"))
      (node (ref "U1") (pin "44") (pinfunction "PD1_(SDAINT1)_44") (pintype "bidirectional"))
    )
    (net (code "14") (name "XTAL-1") (class "Default")
      (node (ref "R1") (pin "1") (pinfunction "1_1") (pintype "input"))
      (node (ref "U1") (pin "34") (pinfunction "XTAL1_34") (pintype "unspecified"))
    )
    (net (code "15") (name "XTAL-2") (class "Default")
      (node (ref "C1") (pin "2") (pinfunction "2_2") (pintype "input"))
      (node (ref "R2") (pin "2") (pinfunction "2_2") (pintype "input"))
      (node (ref "U1") (pin "33") (pinfunction "XTAL2_33") (pintype "output"))
      (node (ref "X1") (pin "3") (pinfunction "OSC2_3") (pintype "unspecified"))
    )
    (net (code "16") (name "unconnected-(RJ3-Pad1)") (class "Default")
      (node (ref "RJ3") (pin "1") (pinfunction "1_1") (pintype "unspecified"))
    )
    (net (code "17") (name "unconnected-(RJ3-Pad2)") (class "Default")
      (node (ref "RJ3") (pin "2") (pinfunction "2_2") (pintype "unspecified"))
    )
    (net (code "18") (name "unconnected-(RJ3-Pad3)") (class "Default")
      (node (ref "RJ3") (pin "3") (pinfunction "3_3") (pintype "unspecified"))
    )
    (net (code "19") (name "unconnected-(RJ3-Pad4)") (class "Default")
      (node (ref "RJ3") (pin "4") (pinfunction "4_4") (pintype "unspecified"))
    )
    (net (code "20") (name "unconnected-(RJ3-Pad5)") (class "Default")
      (node (ref "RJ3") (pin "5") (pinfunction "5_5") (pintype "unspecified"))
    )
    (net (code "21") (name "unconnected-(RJ3-Pad6)") (class "Default")
      (node (ref "RJ3") (pin "6") (pinfunction "6_6") (pintype "unspecified"))
    )
    (net (code "22") (name "unconnected-(RJ3-Pad7)") (class "Default")
      (node (ref "RJ3") (pin "7") (pinfunction "7_7") (pintype "unspecified"))
    )
    (net (code "23") (name "unconnected-(RJ3-Pad8)") (class "Default")
      (node (ref "RJ3") (pin "8") (pinfunction "8_8") (pintype "unspecified"))
    )
    (net (code "24") (name "unconnected-(RJ3-Pad9)") (class "Default")
      (node (ref "RJ3") (pin "9") (pinfunction "9_9") (pintype "unspecified"))
    )
    (net (code "25") (name "unconnected-(RJ3-Pad10)") (class "Default")
      (node (ref "RJ3") (pin "10") (pinfunction "10_10") (pintype "unspecified"))
    )
    (net (code "26") (name "unconnected-(RJ3-Pad11)") (class "Default")
      (node (ref "RJ3") (pin "11") (pinfunction "11_11") (pintype "unspecified"))
    )
    (net (code "27") (name "unconnected-(RJ3-Pad12)") (class "Default")
      (node (ref "RJ3") (pin "12") (pinfunction "12_12") (pintype "unspecified"))
    )
    (net (code "28") (name "unconnected-(RJ3-Pad13)") (class "Default")
      (node (ref "RJ3") (pin "13") (pinfunction "13_13") (pintype "unspecified"))
    )
    (net (code "29") (name "unconnected-(RJ3-Pad14)") (class "Default")
      (node (ref "RJ3") (pin "14") (pinfunction "14_14") (pintype "unspecified"))
    )
    (net (code "30") (name "unconnected-(RJ3-Pad15)") (class "Default")
      (node (ref "RJ3") (pin "15") (pinfunction "15_15") (pintype "unspecified"))
    )
    (net (code "31") (name "unconnected-(RJ3-Pad16)") (class "Default")
      (node (ref "RJ3") (pin "16") (pinfunction "16_16") (pintype "unspecified"))
    )
    (net (code "32") (name "unconnected-(RJ3-Pad17)") (class "Default")
      (node (ref "RJ3") (pin "17") (pinfunction "17_17") (pintype "unspecified"))
    )
    (net (code "33") (name "unconnected-(RJ3-Pad18)") (class "Default")
      (node (ref "RJ3") (pin "18") (pinfunction "18_18") (pintype "unspecified"))
    )
    (net (code "34") (name "unconnected-(RJ3-Pad19)") (class "Default")
      (node (ref "RJ3") (pin "19") (pinfunction "19_19") (pintype "unspecified"))
    )
    (net (code "35") (name "unconnected-(RJ3-Pad20)") (class "Default")
      (node (ref "RJ3") (pin "20") (pinfunction "20_20") (pintype "unspecified"))
    )
    (net (code "36") (name "unconnected-(RJ3-Pad21)") (class "Default")
      (node (ref "RJ3") (pin "21") (pinfunction "21_21") (pintype "unspecified"))
    )
    (net (code "37") (name "unconnected-(RJ3-Pad22)") (class "Default")
      (node (ref "RJ3") (pin "22") (pinfunction "22_22") (pintype "unspecified"))
    )
    (net (code "38") (name "unconnected-(RJ3-Pad23)") (class "Default")
      (node (ref "RJ3") (pin "23") (pinfunction "23_23") (pintype "unspecified"))
    )
    (net (code "39") (name "unconnected-(RJ3-Pad24)") (class "Default")
      (node (ref "RJ3") (pin "24") (pinfunction "24_24") (pintype "unspecified"))
    )
    (net (code "40") (name "unconnected-(RJ3-Pad25)") (class "Default")
      (node (ref "RJ3") (pin "25") (pinfunction "25_25") (pintype "unspecified"))
    )
    (net (code "41") (name "unconnected-(RJ3-Pad26)") (class "Default")
      (node (ref "RJ3") (pin "26") (pinfunction "26_26") (pintype "unspecified"))
    )
    (net (code "42") (name "unconnected-(RJ3-Pad27)") (class "Default")
      (node (ref "RJ3") (pin "27") (pinfunction "27_27") (pintype "unspecified"))
    )
    (net (code "43") (name "unconnected-(RJ3-Pad28)") (class "Default")
      (node (ref "RJ3") (pin "28") (pinfunction "28_28") (pintype "unspecified"))
    )
    (net (code "44") (name "unconnected-(RJ3-Pad29)") (class "Default")
      (node (ref "RJ3") (pin "29") (pinfunction "29_29") (pintype "unspecified"))
    )
    (net (code "45") (name "unconnected-(RJ3-Pad30)") (class "Default")
      (node (ref "RJ3") (pin "30") (pinfunction "30_30") (pintype "unspecified"))
    )
    (net (code "46") (name "unconnected-(RJ3-Pad31)") (class "Default")
      (node (ref "RJ3") (pin "31") (pinfunction "31_31") (pintype "unspecified"))
    )
    (net (code "47") (name "unconnected-(RJ3-Pad32)") (class "Default")
      (node (ref "RJ3") (pin "32") (pinfunction "32_32") (pintype "unspecified"))
    )
    (net (code "48") (name "unconnected-(RJ3-Pad33)") (class "Default")
      (node (ref "RJ3") (pin "33") (pinfunction "33_33") (pintype "unspecified"))
    )
    (net (code "49") (name "unconnected-(RJ3-Pad34)") (class "Default")
      (node (ref "RJ3") (pin "34") (pinfunction "34_34") (pintype "unspecified"))
    )
    (net (code "50") (name "unconnected-(RJ3-Pad35)") (class "Default")
      (node (ref "RJ3") (pin "35") (pinfunction "35_35") (pintype "unspecified"))
    )
    (net (code "51") (name "unconnected-(RJ3-Pad36)") (class "Default")
      (node (ref "RJ3") (pin "36") (pinfunction "36_36") (pintype "unspecified"))
    )
    (net (code "52") (name "unconnected-(RJ3-Pad37)") (class "Default")
      (node (ref "RJ3") (pin "37") (pinfunction "37_37") (pintype "unspecified"))
    )
    (net (code "53") (name "unconnected-(RJ3-Pad38)") (class "Default")
      (node (ref "RJ3") (pin "38") (pinfunction "38_38") (pintype "unspecified"))
    )
    (net (code "54") (name "unconnected-(RJ3-Pad39)") (class "Default")
      (node (ref "RJ3") (pin "39") (pinfunction "39_39") (pintype "unspecified"))
    )
    (net (code "55") (name "unconnected-(RJ3-Pad40)") (class "Default")
      (node (ref "RJ3") (pin "40") (pinfunction "40_40") (pintype "unspecified"))
    )
    (net (code "56") (name "unconnected-(RJ3-Pad41)") (class "Default")
      (node (ref "RJ3") (pin "41") (pinfunction "41_41") (pintype "unspecified"))
    )
    (net (code "57") (name "unconnected-(RJ3-Pad42)") (class "Default")
      (node (ref "RJ3") (pin "42") (pinfunction "42_42") (pintype "unspecified"))
    )
    (net (code "58") (name "unconnected-(RJ3-Pad43)") (class "Default")
      (node (ref "RJ3") (pin "43") (pinfunction "43_43") (pintype "unspecified"))
    )
    (net (code "59") (name "unconnected-(RJ3-Pad44)") (class "Default")
      (node (ref "RJ3") (pin "44") (pinfunction "44_44") (pintype "unspecified"))
    )
    (net (code "60") (name "unconnected-(RJ3-Pad45)") (class "Default")
      (node (ref "RJ3") (pin "45") (pinfunction "45_45") (pintype "unspecified"))
    )
    (net (code "61") (name "unconnected-(RJ3-Pad46)") (class "Default")
      (node (ref "RJ3") (pin "46") (pinfunction "46_46") (pintype "unspecified"))
    )
    (net (code "62") (name "unconnected-(RJ3-Pad47)") (class "Default")
      (node (ref "RJ3") (pin "47") (pinfunction "47_47") (pintype "unspecified"))
    )
    (net (code "63") (name "unconnected-(RJ3-Pad48)") (class "Default")
      (node (ref "RJ3") (pin "48") (pinfunction "48_48") (pintype "unspecified"))
    )
    (net (code "64") (name "unconnected-(RJ3-Pad49)") (class "Default")
      (node (ref "RJ3") (pin "49") (pinfunction "49_49") (pintype "unspecified"))
    )
    (net (code "65") (name "unconnected-(RJ3-Pad50)") (class "Default")
      (node (ref "RJ3") (pin "50") (pinfunction "50_50") (pintype "unspecified"))
    )
    (net (code "66") (name "unconnected-(RJ3-Pad51)") (class "Default")
      (node (ref "RJ3") (pin "51") (pinfunction "51_51") (pintype "unspecified"))
    )
    (net (code "67") (name "unconnected-(RJ3-Pad52)") (class "Default")
      (node (ref "RJ3") (pin "52") (pinfunction "52_52") (pintype "unspecified"))
    )
    (net (code "68") (name "unconnected-(RJ3-Pad53)") (class "Default")
      (node (ref "RJ3") (pin "53") (pinfunction "53_53") (pintype "unspecified"))
    )
    (net (code "69") (name "unconnected-(RJ3-Pad54)") (class "Default")
      (node (ref "RJ3") (pin "54") (pinfunction "54_54") (pintype "unspecified"))
    )
    (net (code "70") (name "unconnected-(RJ3-Pad55)") (class "Default")
      (node (ref "RJ3") (pin "55") (pinfunction "55_55") (pintype "unspecified"))
    )
    (net (code "71") (name "unconnected-(RJ3-Pad56)") (class "Default")
      (node (ref "RJ3") (pin "56") (pinfunction "56_56") (pintype "unspecified"))
    )
    (net (code "72") (name "unconnected-(RJ3-Pad57)") (class "Default")
      (node (ref "RJ3") (pin "57") (pinfunction "57_57") (pintype "unspecified"))
    )
    (net (code "73") (name "unconnected-(RJ3-Pad58)") (class "Default")
      (node (ref "RJ3") (pin "58") (pinfunction "58_58") (pintype "unspecified"))
    )
    (net (code "74") (name "unconnected-(RJ3-Pad59)") (class "Default")
      (node (ref "RJ3") (pin "59") (pinfunction "59_59") (pintype "unspecified"))
    )
    (net (code "75") (name "unconnected-(RJ3-Pad60)") (class "Default")
      (node (ref "RJ3") (pin "60") (pinfunction "60_60") (pintype "unspecified"))
    )
    (net (code "76") (name "unconnected-(RJ3-Pad61)") (class "Default")
      (node (ref "RJ3") (pin "61") (pinfunction "61_61") (pintype "unspecified"))
    )
    (net (code "77") (name "unconnected-(RJ3-Pad62)") (class "Default")
      (node (ref "RJ3") (pin "62") (pinfunction "62_62") (pintype "unspecified"))
    )
    (net (code "78") (name "unconnected-(RJ3-Pad63)") (class "Default")
      (node (ref "RJ3") (pin "63") (pinfunction "63_63") (pintype "unspecified"))
    )
    (net (code "79") (name "unconnected-(RJ3-Pad64)") (class "Default")
      (node (ref "RJ3") (pin "64") (pinfunction "64_64") (pintype "unspecified"))
    )
    (net (code "80") (name "unconnected-(RN1-Pad4)") (class "Default")
      (node (ref "RN1") (pin "4") (pinfunction "4_4") (pintype "input+no_connect"))
    )
    (net (code "81") (name "unconnected-(RN1-Pad5)") (class "Default")
      (node (ref "RN1") (pin "5") (pinfunction "5_5") (pintype "input+no_connect"))
    )
    (net (code "82") (name "unconnected-(U1-PA0_(AD0)-Pad78)") (class "Default")
      (node (ref "U1") (pin "78") (pinfunction "PA0_(AD0)_78") (pintype "bidirectional"))
    )
    (net (code "83") (name "unconnected-(U1-PA1_(AD1)-Pad77)") (class "Default")
      (node (ref "U1") (pin "77") (pinfunction "PA1_(AD1)_77") (pintype "bidirectional"))
    )
    (net (code "84") (name "unconnected-(U1-PA2_(AD2)-Pad76)") (class "Default")
      (node (ref "U1") (pin "76") (pinfunction "PA2_(AD2)_76") (pintype "bidirectional"))
    )
    (net (code "85") (name "unconnected-(U1-PA3_(AD3)-Pad75)") (class "Default")
      (node (ref "U1") (pin "75") (pinfunction "PA3_(AD3)_75") (pintype "bidirectional"))
    )
    (net (code "86") (name "unconnected-(U1-PA4_(AD4)-Pad74)") (class "Default")
      (node (ref "U1") (pin "74") (pinfunction "PA4_(AD4)_74") (pintype "bidirectional"))
    )
    (net (code "87") (name "unconnected-(U1-PA5_(AD5)-Pad73)") (class "Default")
      (node (ref "U1") (pin "73") (pinfunction "PA5_(AD5)_73") (pintype "bidirectional"))
    )
    (net (code "88") (name "unconnected-(U1-PA6_(AD6)-Pad72)") (class "Default")
      (node (ref "U1") (pin "72") (pinfunction "PA6_(AD6)_72") (pintype "bidirectional"))
    )
    (net (code "89") (name "unconnected-(U1-PA7_(AD7)-Pad71)") (class "Default")
      (node (ref "U1") (pin "71") (pinfunction "PA7_(AD7)_71") (pintype "bidirectional"))
    )
    (net (code "90") (name "unconnected-(U1-PB0_(SS#PCINT0)-Pad19)") (class "Default")
      (node (ref "U1") (pin "19") (pinfunction "PB0_(SS#PCINT0)_19") (pintype "bidirectional"))
    )
    (net (code "91") (name "unconnected-(U1-PB4_(OC2APCINT4)-Pad23)") (class "Default")
      (node (ref "U1") (pin "23") (pinfunction "PB4_(OC2APCINT4)_23") (pintype "bidirectional"))
    )
    (net (code "92") (name "unconnected-(U1-PB5_(OC1APCINT5)-Pad24)") (class "Default")
      (node (ref "U1") (pin "24") (pinfunction "PB5_(OC1APCINT5)_24") (pintype "bidirectional"))
    )
    (net (code "93") (name "unconnected-(U1-PB6_(OC1BPCINT6)-Pad25)") (class "Default")
      (node (ref "U1") (pin "25") (pinfunction "PB6_(OC1BPCINT6)_25") (pintype "bidirectional"))
    )
    (net (code "94") (name "unconnected-(U1-PB7_(OC0AOC1CPCINT7)-Pad26)") (class "Default")
      (node (ref "U1") (pin "26") (pinfunction "PB7_(OC0AOC1CPCINT7)_26") (pintype "bidirectional"))
    )
    (net (code "95") (name "unconnected-(U1-PC0_(A8)-Pad53)") (class "Default")
      (node (ref "U1") (pin "53") (pinfunction "PC0_(A8)_53") (pintype "bidirectional"))
    )
    (net (code "96") (name "unconnected-(U1-PC1_(A9)-Pad54)") (class "Default")
      (node (ref "U1") (pin "54") (pinfunction "PC1_(A9)_54") (pintype "bidirectional"))
    )
    (net (code "97") (name "unconnected-(U1-PC2_(A10)-Pad55)") (class "Default")
      (node (ref "U1") (pin "55") (pinfunction "PC2_(A10)_55") (pintype "bidirectional"))
    )
    (net (code "98") (name "unconnected-(U1-PC3_(A11)-Pad56)") (class "Default")
      (node (ref "U1") (pin "56") (pinfunction "PC3_(A11)_56") (pintype "bidirectional"))
    )
    (net (code "99") (name "unconnected-(U1-PC4_(A12)-Pad57)") (class "Default")
      (node (ref "U1") (pin "57") (pinfunction "PC4_(A12)_57") (pintype "bidirectional"))
    )
    (net (code "100") (name "unconnected-(U1-PC5_(A13)-Pad58)") (class "Default")
      (node (ref "U1") (pin "58") (pinfunction "PC5_(A13)_58") (pintype "bidirectional"))
    )
    (net (code "101") (name "unconnected-(U1-PC6_(A14)-Pad59)") (class "Default")
      (node (ref "U1") (pin "59") (pinfunction "PC6_(A14)_59") (pintype "bidirectional"))
    )
    (net (code "102") (name "unconnected-(U1-PC7_(A15)-Pad60)") (class "Default")
      (node (ref "U1") (pin "60") (pinfunction "PC7_(A15)_60") (pintype "bidirectional"))
    )
    (net (code "103") (name "unconnected-(U1-PD2_(RXD1INT2)-Pad45)") (class "Default")
      (node (ref "U1") (pin "45") (pinfunction "PD2_(RXD1INT2)_45") (pintype "bidirectional"))
    )
    (net (code "104") (name "unconnected-(U1-PD3_(TXD1INT3)-Pad46)") (class "Default")
      (node (ref "U1") (pin "46") (pinfunction "PD3_(TXD1INT3)_46") (pintype "bidirectional"))
    )
    (net (code "105") (name "unconnected-(U1-PD4_(ICP1)-Pad47)") (class "Default")
      (node (ref "U1") (pin "47") (pinfunction "PD4_(ICP1)_47") (pintype "bidirectional"))
    )
    (net (code "106") (name "unconnected-(U1-PD5_(XCK1)-Pad48)") (class "Default")
      (node (ref "U1") (pin "48") (pinfunction "PD5_(XCK1)_48") (pintype "bidirectional"))
    )
    (net (code "107") (name "unconnected-(U1-PD6_(T1)-Pad49)") (class "Default")
      (node (ref "U1") (pin "49") (pinfunction "PD6_(T1)_49") (pintype "bidirectional"))
    )
    (net (code "108") (name "unconnected-(U1-PD7_(T0)-Pad50)") (class "Default")
      (node (ref "U1") (pin "50") (pinfunction "PD7_(T0)_50") (pintype "bidirectional"))
    )
    (net (code "109") (name "unconnected-(U1-PE0_(RXD0PCINT8)-Pad2)") (class "Default")
      (node (ref "U1") (pin "2") (pinfunction "PE0_(RXD0PCINT8)_2") (pintype "bidirectional"))
    )
    (net (code "110") (name "unconnected-(U1-PE1_(TXD0)-Pad3)") (class "Default")
      (node (ref "U1") (pin "3") (pinfunction "PE1_(TXD0)_3") (pintype "bidirectional"))
    )
    (net (code "111") (name "unconnected-(U1-PE2_(XCK0AIN0)-Pad4)") (class "Default")
      (node (ref "U1") (pin "4") (pinfunction "PE2_(XCK0AIN0)_4") (pintype "bidirectional"))
    )
    (net (code "112") (name "unconnected-(U1-PE3_(OC3AAIN1)-Pad5)") (class "Default")
      (node (ref "U1") (pin "5") (pinfunction "PE3_(OC3AAIN1)_5") (pintype "bidirectional"))
    )
    (net (code "113") (name "unconnected-(U1-PE4_(OC3BINT4)-Pad6)") (class "Default")
      (node (ref "U1") (pin "6") (pinfunction "PE4_(OC3BINT4)_6") (pintype "bidirectional"))
    )
    (net (code "114") (name "unconnected-(U1-PE5_(OC3CINT5)-Pad7)") (class "Default")
      (node (ref "U1") (pin "7") (pinfunction "PE5_(OC3CINT5)_7") (pintype "bidirectional"))
    )
    (net (code "115") (name "unconnected-(U1-PE6_(T3INT6)-Pad8)") (class "Default")
      (node (ref "U1") (pin "8") (pinfunction "PE6_(T3INT6)_8") (pintype "bidirectional"))
    )
    (net (code "116") (name "unconnected-(U1-PE7_(CLKOICP3INT7)-Pad9)") (class "Default")
      (node (ref "U1") (pin "9") (pinfunction "PE7_(CLKOICP3INT7)_9") (pintype "bidirectional"))
    )
    (net (code "117") (name "unconnected-(U1-PF0_(ADC0)-Pad97)") (class "Default")
      (node (ref "U1") (pin "97") (pinfunction "PF0_(ADC0)_97") (pintype "bidirectional"))
    )
    (net (code "118") (name "unconnected-(U1-PF1_(ADC1)-Pad96)") (class "Default")
      (node (ref "U1") (pin "96") (pinfunction "PF1_(ADC1)_96") (pintype "bidirectional"))
    )
    (net (code "119") (name "unconnected-(U1-PF2_(ADC2)-Pad95)") (class "Default")
      (node (ref "U1") (pin "95") (pinfunction "PF2_(ADC2)_95") (pintype "bidirectional"))
    )
    (net (code "120") (name "unconnected-(U1-PF3_(ADC3)-Pad94)") (class "Default")
      (node (ref "U1") (pin "94") (pinfunction "PF3_(ADC3)_94") (pintype "bidirectional"))
    )
    (net (code "121") (name "unconnected-(U1-PF4_(ADC4TCK)-Pad93)") (class "Default")
      (node (ref "U1") (pin "93") (pinfunction "PF4_(ADC4TCK)_93") (pintype "bidirectional"))
    )
    (net (code "122") (name "unconnected-(U1-PF5_(ADC5TMS)-Pad92)") (class "Default")
      (node (ref "U1") (pin "92") (pinfunction "PF5_(ADC5TMS)_92") (pintype "bidirectional"))
    )
    (net (code "123") (name "unconnected-(U1-PF6_(ADC6TDO)-Pad91)") (class "Default")
      (node (ref "U1") (pin "91") (pinfunction "PF6_(ADC6TDO)_91") (pintype "bidirectional"))
    )
    (net (code "124") (name "unconnected-(U1-PF7_(ADC7TDI)-Pad90)") (class "Default")
      (node (ref "U1") (pin "90") (pinfunction "PF7_(ADC7TDI)_90") (pintype "bidirectional"))
    )
    (net (code "125") (name "unconnected-(U1-PG0_(WR#)-Pad51)") (class "Default")
      (node (ref "U1") (pin "51") (pinfunction "PG0_(WR#)_51") (pintype "bidirectional"))
    )
    (net (code "126") (name "unconnected-(U1-PG1_(RD#)-Pad52)") (class "Default")
      (node (ref "U1") (pin "52") (pinfunction "PG1_(RD#)_52") (pintype "bidirectional"))
    )
    (net (code "127") (name "unconnected-(U1-PG2_(ALE)-Pad70)") (class "Default")
      (node (ref "U1") (pin "70") (pinfunction "PG2_(ALE)_70") (pintype "bidirectional"))
    )
    (net (code "128") (name "unconnected-(U1-PG3_(TOSC2)-Pad28)") (class "Default")
      (node (ref "U1") (pin "28") (pinfunction "PG3_(TOSC2)_28") (pintype "bidirectional"))
    )
    (net (code "129") (name "unconnected-(U1-PG4_(TOSC1)-Pad29)") (class "Default")
      (node (ref "U1") (pin "29") (pinfunction "PG4_(TOSC1)_29") (pintype "bidirectional"))
    )
    (net (code "130") (name "unconnected-(U1-PG5_(OC0B)-Pad1)") (class "Default")
      (node (ref "U1") (pin "1") (pinfunction "PG5_(OC0B)_1") (pintype "bidirectional"))
    )
    (net (code "131") (name "unconnected-(U1-PH0_(RXD2)-Pad12)") (class "Default")
      (node (ref "U1") (pin "12") (pinfunction "PH0_(RXD2)_12") (pintype "bidirectional"))
    )
    (net (code "132") (name "unconnected-(U1-PH1_(TXD2)-Pad13)") (class "Default")
      (node (ref "U1") (pin "13") (pinfunction "PH1_(TXD2)_13") (pintype "bidirectional"))
    )
    (net (code "133") (name "unconnected-(U1-PH2_(XCK2)-Pad14)") (class "Default")
      (node (ref "U1") (pin "14") (pinfunction "PH2_(XCK2)_14") (pintype "bidirectional"))
    )
    (net (code "134") (name "unconnected-(U1-PH3_(OC4A)-Pad15)") (class "Default")
      (node (ref "U1") (pin "15") (pinfunction "PH3_(OC4A)_15") (pintype "bidirectional"))
    )
    (net (code "135") (name "unconnected-(U1-PH4_(OC4B)-Pad16)") (class "Default")
      (node (ref "U1") (pin "16") (pinfunction "PH4_(OC4B)_16") (pintype "bidirectional"))
    )
    (net (code "136") (name "unconnected-(U1-PH5_(OC4C)-Pad17)") (class "Default")
      (node (ref "U1") (pin "17") (pinfunction "PH5_(OC4C)_17") (pintype "bidirectional"))
    )
    (net (code "137") (name "unconnected-(U1-PH6_(OC2B)-Pad18)") (class "Default")
      (node (ref "U1") (pin "18") (pinfunction "PH6_(OC2B)_18") (pintype "bidirectional"))
    )
    (net (code "138") (name "unconnected-(U1-PH7_(T4)-Pad27)") (class "Default")
      (node (ref "U1") (pin "27") (pinfunction "PH7_(T4)_27") (pintype "bidirectional"))
    )
    (net (code "139") (name "unconnected-(U1-PJ0_(RXD3PCINT9)-Pad63)") (class "Default")
      (node (ref "U1") (pin "63") (pinfunction "PJ0_(RXD3PCINT9)_63") (pintype "bidirectional"))
    )
    (net (code "140") (name "unconnected-(U1-PJ1_(TXD3PCINT10)-Pad64)") (class "Default")
      (node (ref "U1") (pin "64") (pinfunction "PJ1_(TXD3PCINT10)_64") (pintype "bidirectional"))
    )
    (net (code "141") (name "unconnected-(U1-PJ2_(XCK3PCINT11)-Pad65)") (class "Default")
      (node (ref "U1") (pin "65") (pinfunction "PJ2_(XCK3PCINT11)_65") (pintype "bidirectional"))
    )
    (net (code "142") (name "unconnected-(U1-PJ3_(PCINT12)-Pad66)") (class "Default")
      (node (ref "U1") (pin "66") (pinfunction "PJ3_(PCINT12)_66") (pintype "bidirectional"))
    )
    (net (code "143") (name "unconnected-(U1-PJ4_(PCINT13)-Pad67)") (class "Default")
      (node (ref "U1") (pin "67") (pinfunction "PJ4_(PCINT13)_67") (pintype "bidirectional"))
    )
    (net (code "144") (name "unconnected-(U1-PJ5_(PCINT14)-Pad68)") (class "Default")
      (node (ref "U1") (pin "68") (pinfunction "PJ5_(PCINT14)_68") (pintype "bidirectional"))
    )
    (net (code "145") (name "unconnected-(U1-PJ6_(PCINT15)-Pad69)") (class "Default")
      (node (ref "U1") (pin "69") (pinfunction "PJ6_(PCINT15)_69") (pintype "bidirectional"))
    )
    (net (code "146") (name "unconnected-(U1-PJ7-Pad79)") (class "Default")
      (node (ref "U1") (pin "79") (pinfunction "PJ7_79") (pintype "bidirectional"))
    )
    (net (code "147") (name "unconnected-(U1-PK0_(ADC8PCINT16)-Pad89)") (class "Default")
      (node (ref "U1") (pin "89") (pinfunction "PK0_(ADC8PCINT16)_89") (pintype "bidirectional"))
    )
    (net (code "148") (name "unconnected-(U1-PK1_(ADC9PCINT17)-Pad88)") (class "Default")
      (node (ref "U1") (pin "88") (pinfunction "PK1_(ADC9PCINT17)_88") (pintype "bidirectional"))
    )
    (net (code "149") (name "unconnected-(U1-PK2_(ADC10PCINT18)-Pad87)") (class "Default")
      (node (ref "U1") (pin "87") (pinfunction "PK2_(ADC10PCINT18)_87") (pintype "bidirectional"))
    )
    (net (code "150") (name "unconnected-(U1-PK3_(ADC11PCINT19)-Pad86)") (class "Default")
      (node (ref "U1") (pin "86") (pinfunction "PK3_(ADC11PCINT19)_86") (pintype "bidirectional"))
    )
    (net (code "151") (name "unconnected-(U1-PK4_(ADC12PCINT20)-Pad85)") (class "Default")
      (node (ref "U1") (pin "85") (pinfunction "PK4_(ADC12PCINT20)_85") (pintype "bidirectional"))
    )
    (net (code "152") (name "unconnected-(U1-PK5_(ADC13PCINT21)-Pad84)") (class "Default")
      (node (ref "U1") (pin "84") (pinfunction "PK5_(ADC13PCINT21)_84") (pintype "bidirectional"))
    )
    (net (code "153") (name "unconnected-(U1-PK6_(ADC14PCINT22)-Pad83)") (class "Default")
      (node (ref "U1") (pin "83") (pinfunction "PK6_(ADC14PCINT22)_83") (pintype "bidirectional"))
    )
    (net (code "154") (name "unconnected-(U1-PK7_(ADC15PCINT23)-Pad82)") (class "Default")
      (node (ref "U1") (pin "82") (pinfunction "PK7_(ADC15PCINT23)_82") (pintype "bidirectional"))
    )
    (net (code "155") (name "unconnected-(U1-PL0_(ICP4)-Pad35)") (class "Default")
      (node (ref "U1") (pin "35") (pinfunction "PL0_(ICP4)_35") (pintype "bidirectional"))
    )
    (net (code "156") (name "unconnected-(U1-PL1_(ICP5)-Pad36)") (class "Default")
      (node (ref "U1") (pin "36") (pinfunction "PL1_(ICP5)_36") (pintype "bidirectional"))
    )
    (net (code "157") (name "unconnected-(U1-PL2_(T5)-Pad37)") (class "Default")
      (node (ref "U1") (pin "37") (pinfunction "PL2_(T5)_37") (pintype "bidirectional"))
    )
    (net (code "158") (name "unconnected-(U1-PL3_(OC5A)-Pad38)") (class "Default")
      (node (ref "U1") (pin "38") (pinfunction "PL3_(OC5A)_38") (pintype "bidirectional"))
    )
    (net (code "159") (name "unconnected-(U1-PL4_(OC5B)-Pad39)") (class "Default")
      (node (ref "U1") (pin "39") (pinfunction "PL4_(OC5B)_39") (pintype "bidirectional"))
    )
    (net (code "160") (name "unconnected-(U1-PL5_(OC5C)-Pad40)") (class "Default")
      (node (ref "U1") (pin "40") (pinfunction "PL5_(OC5C)_40") (pintype "bidirectional"))
    )
    (net (code "161") (name "unconnected-(U1-PL6-Pad41)") (class "Default")
      (node (ref "U1") (pin "41") (pinfunction "PL6_41") (pintype "bidirectional"))
    )
    (net (code "162") (name "unconnected-(U1-PL7-Pad42)") (class "Default")
      (node (ref "U1") (pin "42") (pinfunction "PL7_42") (pintype "bidirectional"))
    )
  )
)
